# BoardTop.net
KiCad netlist of a schematic drawn in Altium Designer
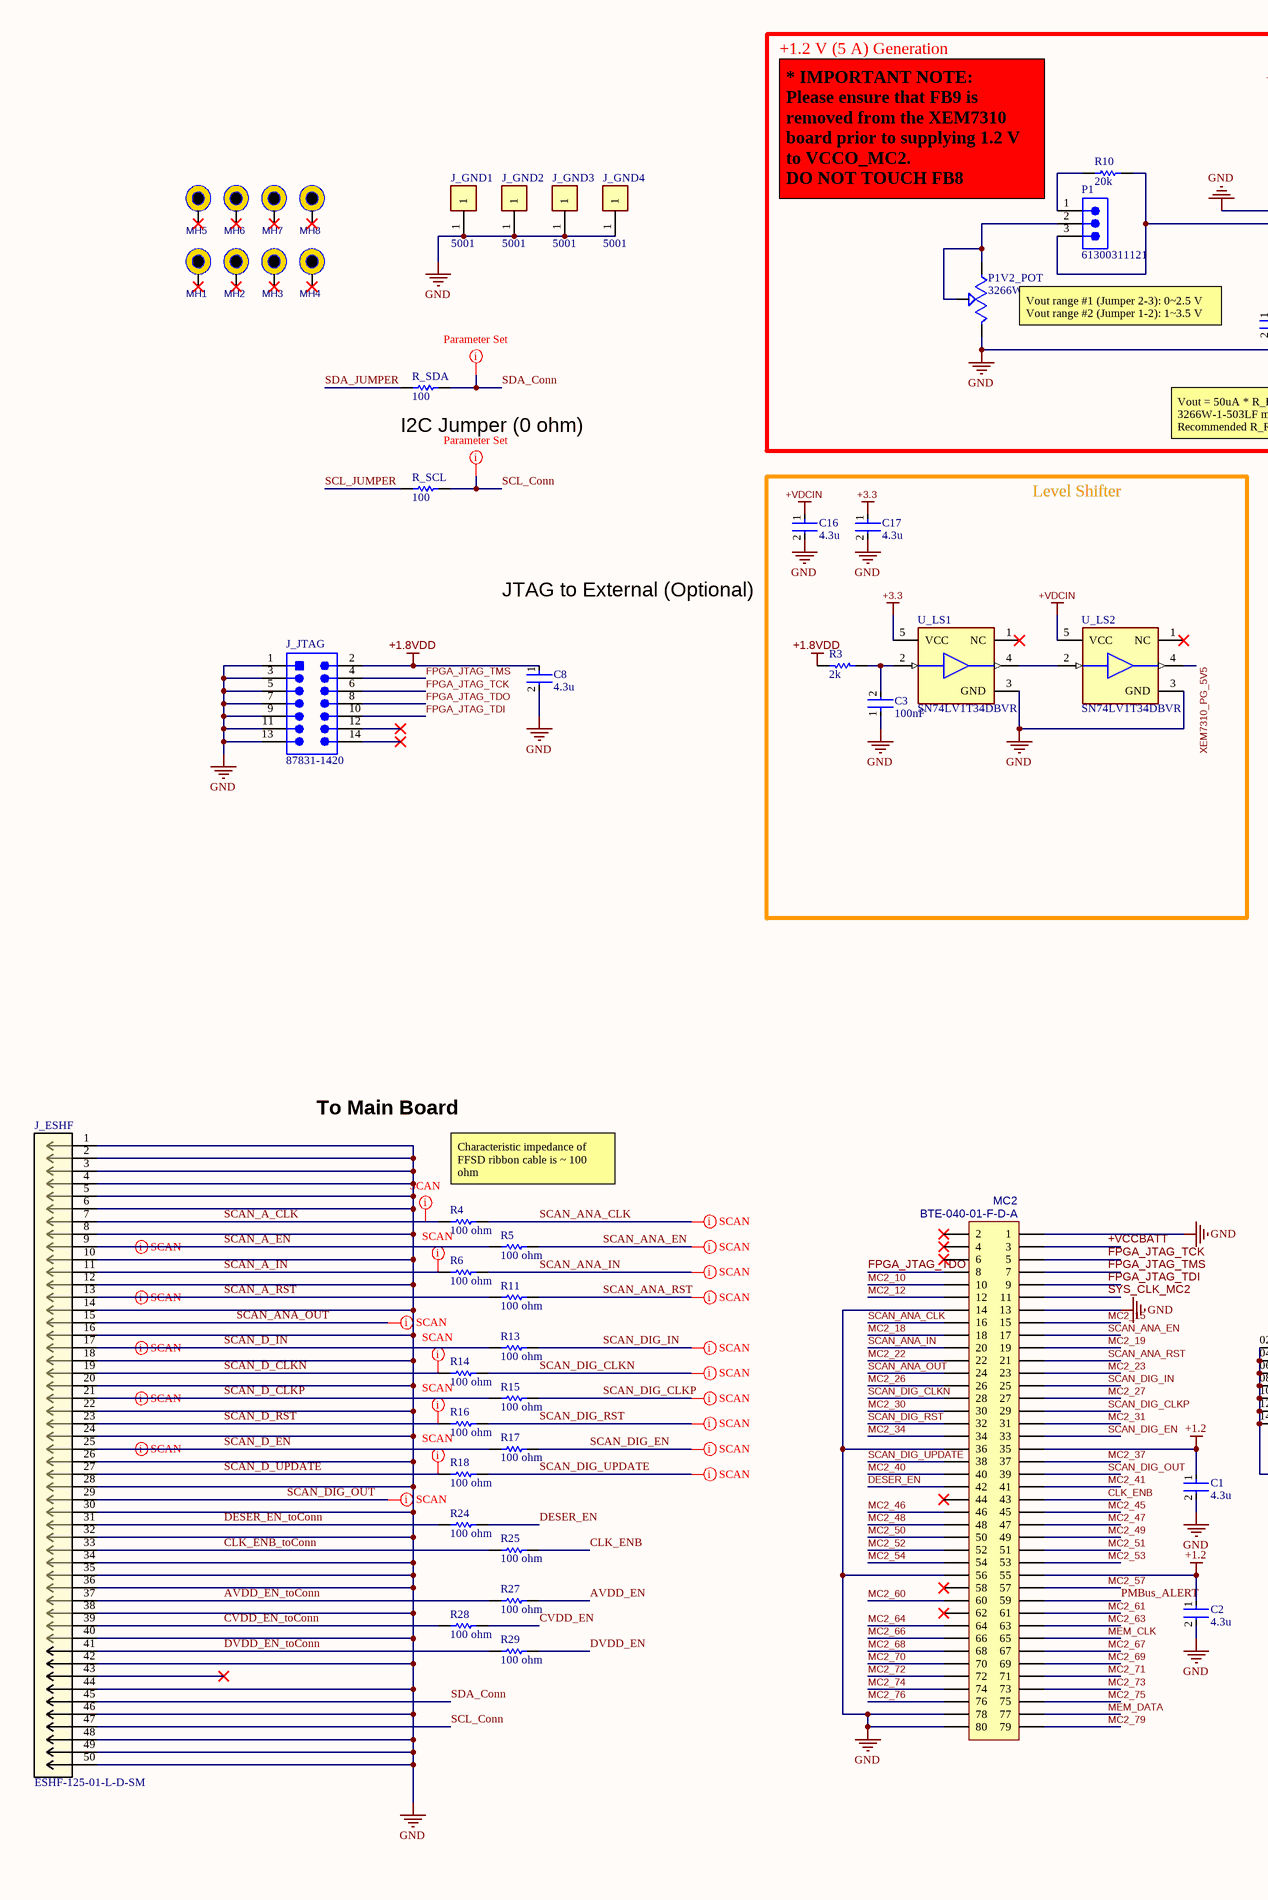
[diagram p0: BoardTop.SchDoc, left]
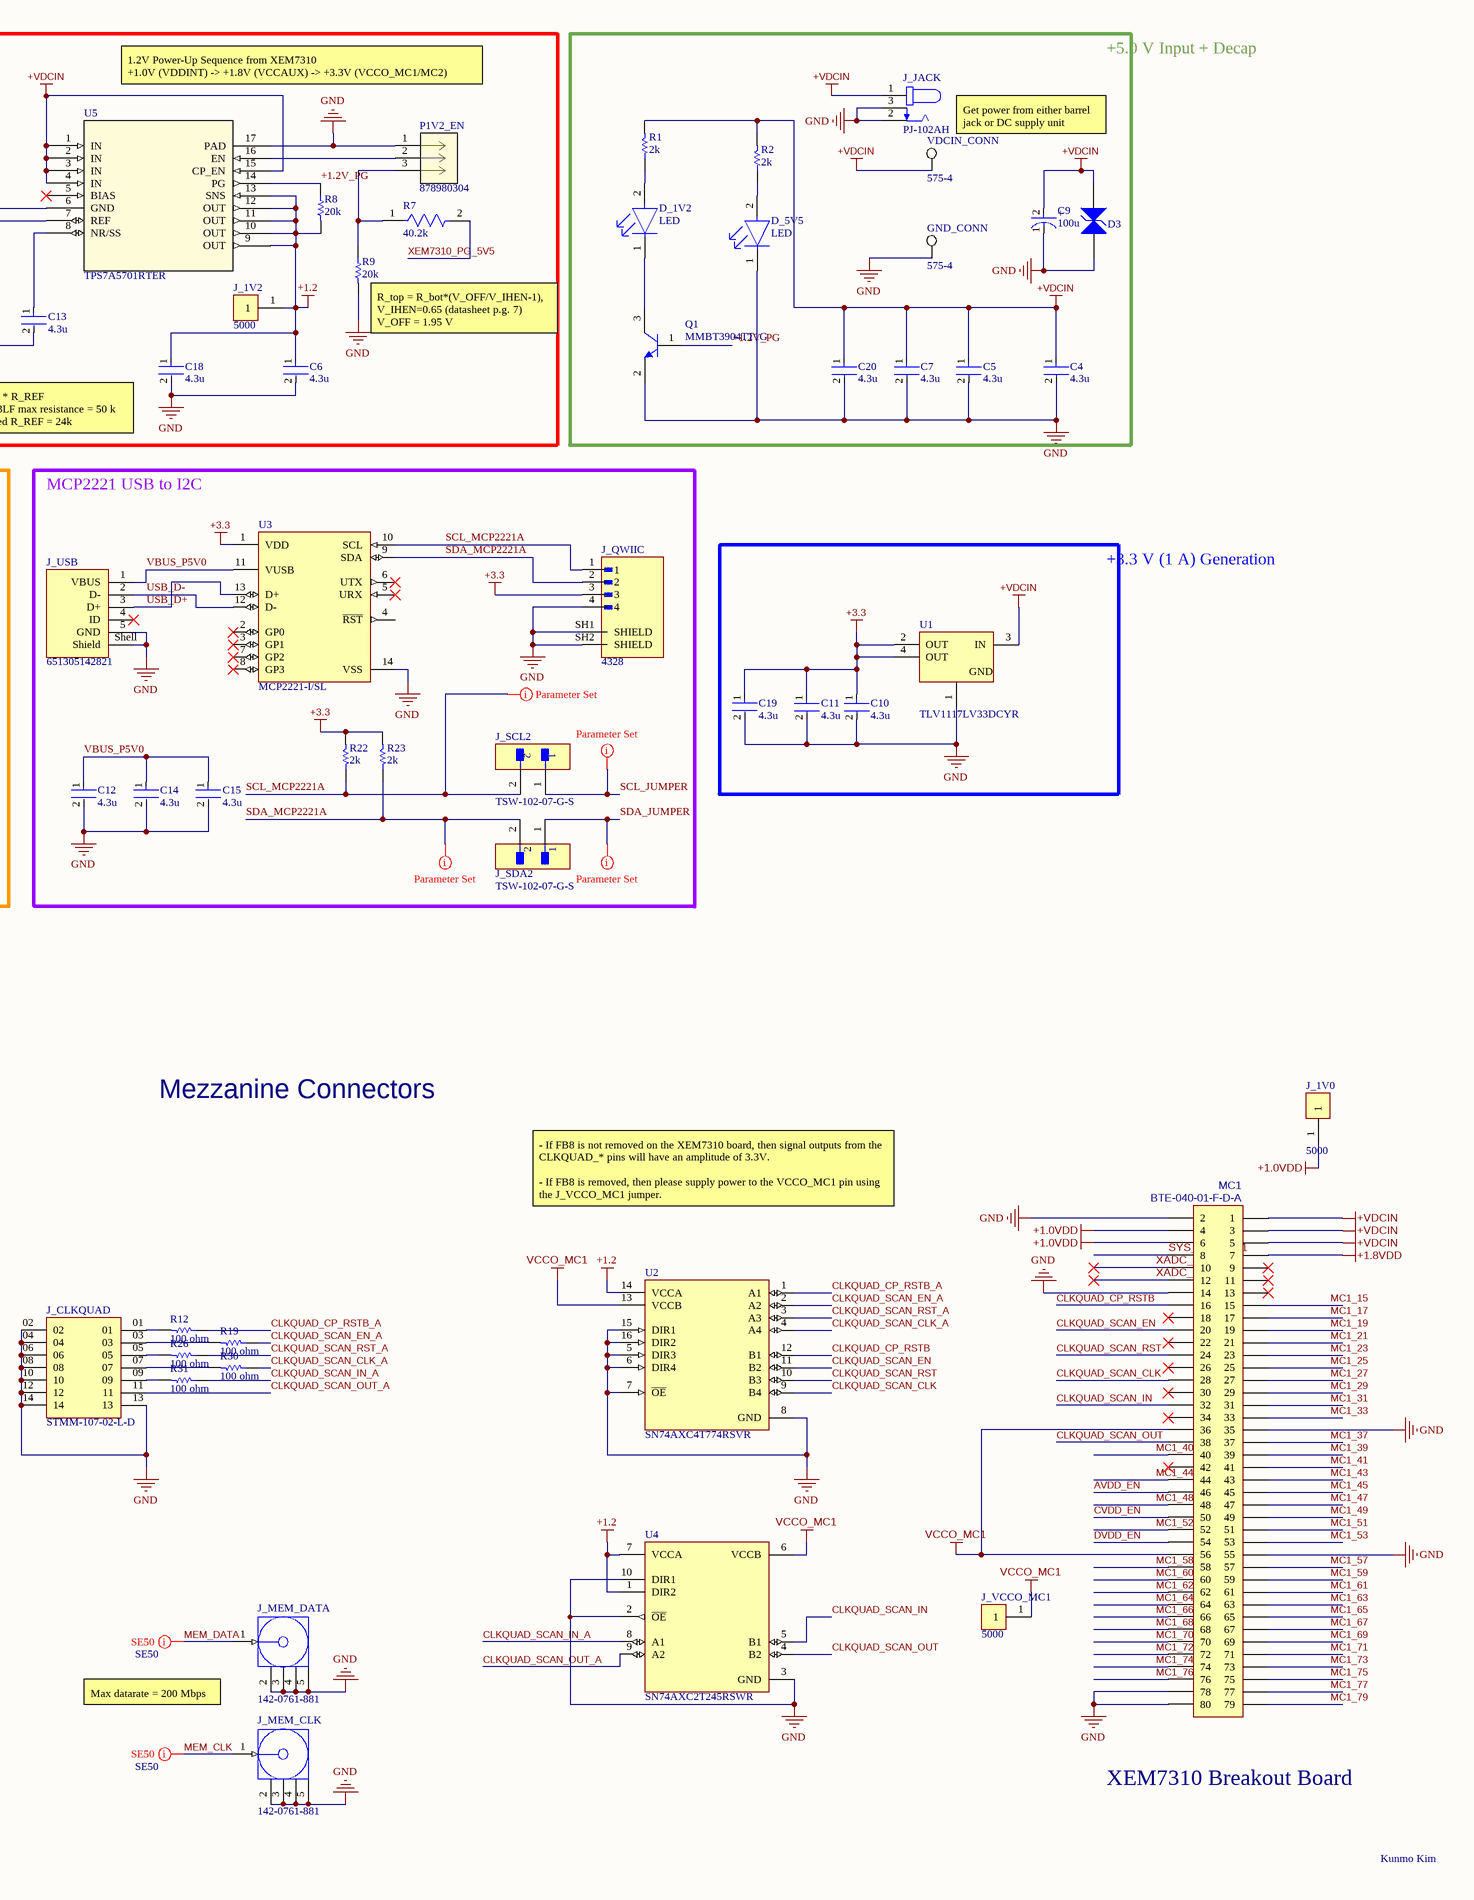
[diagram p1: BoardTop.SchDoc, right]

(export (version "E")
  (design (tool "Eeschema 10.0.6"))
  (components
    (comp (ref "C1")
      (value "4.3u")
      (footprint "FP-LLL1U4-0_05-IPC_C")
      (description "Cap Ceramic Monolithic 4.3uF 20% 4V X5R 15% 02404 (0610M)")
      (fields (field (name "TOLERANCE") "20%"))
      (libsource (lib "Altium Content Vault") (part "b4654b650e69147ec39a6b967a45e02"))
    )
    (comp (ref "C2")
      (value "4.3u")
      (footprint "FP-LLL1U4-0_05-IPC_C")
      (description "Cap Ceramic Monolithic 4.3uF 20% 4V X5R 15% 02404 (0610M)")
      (fields (field (name "TOLERANCE") "20%"))
      (libsource (lib "Altium Content Vault") (part "b4654b650e69147ec39a6b967a45e02"))
    )
    (comp (ref "C3")
      (value "100nF")
      (footprint "FP-0603-L_1_6_0_15-W_0_81-MFG")
      (description "General Purpose Ceramic Capacitor, 0603, 100nF, 10%, X7R, 15%, 50V")
      (fields (field (name "TOLERANCE") "10%") (field (name "VOLTAGE") "50V"))
      (libsource (lib "Altium Content Vault") (part "02cd4be3c70576c341d710602a673aa"))
    )
    (comp (ref "C4")
      (value "4.3u")
      (footprint "FP-LLL1U4-0_05-IPC_C")
      (description "Cap Ceramic Monolithic 4.3uF 20% 4V X5R 15% 02404 (0610M)")
      (fields (field (name "TOLERANCE") "20%"))
      (libsource (lib "Altium Content Vault") (part "b4654b650e69147ec39a6b967a45e02"))
    )
    (comp (ref "C5")
      (value "4.3u")
      (footprint "FP-LLL1U4-0_05-IPC_C")
      (description "Cap Ceramic Monolithic 4.3uF 20% 4V X5R 15% 02404 (0610M)")
      (fields (field (name "TOLERANCE") "20%"))
      (libsource (lib "Altium Content Vault") (part "b4654b650e69147ec39a6b967a45e02"))
    )
    (comp (ref "C6")
      (value "4.3u")
      (footprint "FP-LLL1U4-0_05-IPC_C")
      (description "Cap Ceramic Monolithic 4.3uF 20% 4V X5R 15% 02404 (0610M)")
      (fields (field (name "TOLERANCE") "20%"))
      (libsource (lib "Altium Content Vault") (part "b4654b650e69147ec39a6b967a45e02"))
    )
    (comp (ref "C7")
      (value "4.3u")
      (footprint "FP-LLL1U4-0_05-IPC_C")
      (description "Cap Ceramic Monolithic 4.3uF 20% 4V X5R 15% 02404 (0610M)")
      (fields (field (name "TOLERANCE") "20%"))
      (libsource (lib "Altium Content Vault") (part "b4654b650e69147ec39a6b967a45e02"))
    )
    (comp (ref "C8")
      (value "4.3u")
      (footprint "FP-LLL1U4-0_05-IPC_C")
      (description "Cap Ceramic Monolithic 4.3uF 20% 4V X5R 15% 02404 (0610M)")
      (fields (field (name "TOLERANCE") "20%"))
      (libsource (lib "Altium Content Vault") (part "b4654b650e69147ec39a6b967a45e02"))
    )
    (comp (ref "C9")
      (value "100u")
      (footprint "FP-CX-MFG")
      (description "CAP ALUM POLY 100UF 20% 6.3V SMD")
      (fields (field (name "VOLTAGE") "6.3V") (field (name "TOLERANCE") "20%"))
      (libsource (lib "cap_SP_100uF") (part "CMP-05427-000056-1"))
    )
    (comp (ref "C10")
      (value "4.3u")
      (footprint "FP-LLL1U4-0_05-IPC_C")
      (description "Cap Ceramic Monolithic 4.3uF 20% 4V X5R 15% 02404 (0610M)")
      (fields (field (name "TOLERANCE") "20%"))
      (libsource (lib "Altium Content Vault") (part "b4654b650e69147ec39a6b967a45e02"))
    )
    (comp (ref "C11")
      (value "4.3u")
      (footprint "FP-LLL1U4-0_05-IPC_C")
      (description "Cap Ceramic Monolithic 4.3uF 20% 4V X5R 15% 02404 (0610M)")
      (fields (field (name "TOLERANCE") "20%"))
      (libsource (lib "Altium Content Vault") (part "b4654b650e69147ec39a6b967a45e02"))
    )
    (comp (ref "C12")
      (value "4.3u")
      (footprint "FP-LLL1U4-0_05-IPC_C")
      (description "Cap Ceramic Monolithic 4.3uF 20% 4V X5R 15% 02404 (0610M)")
      (fields (field (name "TOLERANCE") "20%"))
      (libsource (lib "Altium Content Vault") (part "b4654b650e69147ec39a6b967a45e02"))
    )
    (comp (ref "C13")
      (value "4.3u")
      (footprint "FP-LLL1U4-0_05-IPC_C")
      (description "Cap Ceramic Monolithic 4.3uF 20% 4V X5R 15% 02404 (0610M)")
      (fields (field (name "TOLERANCE") "20%"))
      (libsource (lib "Altium Content Vault") (part "b4654b650e69147ec39a6b967a45e02"))
    )
    (comp (ref "C14")
      (value "4.3u")
      (footprint "FP-LLL1U4-0_05-IPC_C")
      (description "Cap Ceramic Monolithic 4.3uF 20% 4V X5R 15% 02404 (0610M)")
      (fields (field (name "TOLERANCE") "20%"))
      (libsource (lib "Altium Content Vault") (part "b4654b650e69147ec39a6b967a45e02"))
    )
    (comp (ref "C15")
      (value "4.3u")
      (footprint "FP-LLL1U4-0_05-IPC_C")
      (description "Cap Ceramic Monolithic 4.3uF 20% 4V X5R 15% 02404 (0610M)")
      (fields (field (name "TOLERANCE") "20%"))
      (libsource (lib "Altium Content Vault") (part "b4654b650e69147ec39a6b967a45e02"))
    )
    (comp (ref "C16")
      (value "4.3u")
      (footprint "FP-LLL1U4-0_05-IPC_C")
      (description "Cap Ceramic Monolithic 4.3uF 20% 4V X5R 15% 02404 (0610M)")
      (fields (field (name "TOLERANCE") "20%"))
      (libsource (lib "Altium Content Vault") (part "b4654b650e69147ec39a6b967a45e02"))
    )
    (comp (ref "C17")
      (value "4.3u")
      (footprint "FP-LLL1U4-0_05-IPC_C")
      (description "Cap Ceramic Monolithic 4.3uF 20% 4V X5R 15% 02404 (0610M)")
      (fields (field (name "TOLERANCE") "20%"))
      (libsource (lib "Altium Content Vault") (part "b4654b650e69147ec39a6b967a45e02"))
    )
    (comp (ref "C18")
      (value "4.3u")
      (footprint "FP-LLL1U4-0_05-IPC_C")
      (description "Cap Ceramic Monolithic 4.3uF 20% 4V X5R 15% 02404 (0610M)")
      (fields (field (name "TOLERANCE") "20%"))
      (libsource (lib "Altium Content Vault") (part "b4654b650e69147ec39a6b967a45e02"))
    )
    (comp (ref "C19")
      (value "4.3u")
      (footprint "FP-LLL1U4-0_05-IPC_C")
      (description "Cap Ceramic Monolithic 4.3uF 20% 4V X5R 15% 02404 (0610M)")
      (fields (field (name "TOLERANCE") "20%"))
      (libsource (lib "Altium Content Vault") (part "b4654b650e69147ec39a6b967a45e02"))
    )
    (comp (ref "C20")
      (value "4.3u")
      (footprint "FP-LLL1U4-0_05-IPC_C")
      (description "Cap Ceramic Monolithic 4.3uF 20% 4V X5R 15% 02404 (0610M)")
      (fields (field (name "TOLERANCE") "20%"))
      (libsource (lib "Altium Content Vault") (part "b4654b650e69147ec39a6b967a45e02"))
    )
    (comp (ref "D3")
      (value "SMAJ6.0CAHE3/5A")
      (footprint "VISH-DO-214AC-2_L")
      (fields (field (name "MANUFACTURER") "Vishay Semiconductor"))
      (libsource (lib "SMAJ6p0CAHE3") (part "CMP-0548-00108-2"))
    )
    (comp (ref "D_1V2")
      (value "LED")
      (footprint "FP-LTST-C190KGKT-MFG")
      (description "LED GREEN CLEAR CHIP SMD")
      (libsource (lib "LTST-C190KGKT") (part "CMP-2000-05197-2"))
    )
    (comp (ref "D_5V5")
      (value "LED")
      (footprint "FP-LTST-C190KGKT-MFG")
      (description "LED GREEN CLEAR CHIP SMD")
      (libsource (lib "LTST-C190KGKT") (part "CMP-2000-05197-2"))
    )
    (comp (ref "GND_CONN")
      (value "575-4")
      (footprint "KSTN-575-4")
      (description "Banana Jack, Non-Insulated, 1-Pin THD, RoHS, Bulk")
      (fields (field (name "MANUFACTURER") "Keystone-Electronics"))
      (libsource (lib "Altium Content Vault") (part "TESTPOINT_WHITE"))
    )
    (comp (ref "J_1V0")
      (value "5000")
      (footprint "FP-5000-MFG")
      (description "PC TEST POINT MINIATURE RED")
      (libsource (lib "") (part "CMP-19636-000027-1_1"))
    )
    (comp (ref "J_1V2")
      (value "5000")
      (footprint "FP-5000-MFG")
      (description "PC TEST POINT MINIATURE RED")
      (libsource (lib "TP_5000") (part "CMP-19636-000027-1"))
    )
    (comp (ref "J_CLKQUAD")
      (value "STMM-107-02-L-D")
      (footprint "SAMTEC_STMM-107-02-L-D")
      (description "Connector Header Surface Mount 14 position 0.079 (2.00mm)")
      (fields (field (name "MF") "Samtec") (field (name "DIGI-KEY_PART_NUMBER") "STMM-107-02-L-D-SM-TR-ND"))
      (libsource (lib "STMM-107-02-L-D") (part "STMM-107-02-L-D"))
    )
    (comp (ref "J_ESHF")
      (value "ESHF-125-01-L-D-SM")
      (footprint "CONN_ESHF-125-01-x-D-SM_SAI")
      (description "No Description Available")
      (libsource (lib "FPGA_breakout_board") (part "ESHF-125-01-L-D-SM"))
    )
    (comp (ref "J_GND1")
      (value "5001")
      (footprint "FP-5001-MFG")
      (description "PC TEST POINT MINIATURE BLACK")
      (libsource (lib "TP_5001") (part "CMP-2000-05181-2"))
    )
    (comp (ref "J_GND2")
      (value "5001")
      (footprint "FP-5001-MFG")
      (description "PC TEST POINT MINIATURE BLACK")
      (libsource (lib "TP_5001") (part "CMP-2000-05181-2"))
    )
    (comp (ref "J_GND3")
      (value "5001")
      (footprint "FP-5001-MFG")
      (description "PC TEST POINT MINIATURE BLACK")
      (libsource (lib "TP_5001") (part "CMP-2000-05181-2"))
    )
    (comp (ref "J_GND4")
      (value "5001")
      (footprint "FP-5001-MFG")
      (description "PC TEST POINT MINIATURE BLACK")
      (libsource (lib "TP_5001") (part "CMP-2000-05181-2"))
    )
    (comp (ref "J_JACK")
      (value "PJ-102AH")
      (footprint "CUI_PJ-102AH")
      (description "2.0 x 6.5 mm, 5.0 A, Horizontal, Through Hole, Tapered Pins, Dc Power Jack Connector")
      (fields (field (name "MF") "Same Sky"))
      (libsource (lib "PJ-102AH") (part "PJ-102AH"))
    )
    (comp (ref "J_JTAG")
      (value "87831-1420")
      (footprint "MOLEX-87831-1420_V")
      (description "Header, Pitch 2 mm, 2 x 7 Position, Height 6.4 mm, Tail Length 2.5 mm, -55 to 105 degC, RoHS, Tube")
      (fields (field (name "MANUFACTURER") "Molex"))
      (libsource (lib "JTAG_connector") (part "CMP-2000-05240-1"))
    )
    (comp (ref "J_MEM_CLK")
      (value "142-0761-881")
      (footprint "EMSN-142-0761-881-5_V")
      (fields (field (name "MANUFACTURER") "Emerson Network Power"))
      (libsource (lib "SMA_connector_A") (part "CMP-0839-00001-1"))
    )
    (comp (ref "J_MEM_DATA")
      (value "142-0761-881")
      (footprint "EMSN-142-0761-881-5_V")
      (fields (field (name "MANUFACTURER") "Emerson Network Power"))
      (libsource (lib "SMA_connector_A") (part "CMP-0839-00001-1"))
    )
    (comp (ref "J_QWIIC")
      (value "4328")
      (footprint "ADAFRUIT_4328")
      (description "Adafruit Accessories JST SH 4-pin Vertical Connector (10-pack) - Qwiic Compatible")
      (fields (field (name "MF") "Adafruit"))
      (libsource (lib "4328") (part "4328"))
    )
    (comp (ref "J_SCL2")
      (value "TSW-102-07-G-S")
      (footprint "FP-TSW-102-07-G-S-MFG")
      (description "CONN HEADER VERT 2POS 2.54MM")
      (fields
        (field (name "MANUFACTURER") "Samtec")
        (field (name "OCTOPART") "https://octopart.com/tsw-102-07-g-s-samtec-272197")
      )
      (libsource (lib "") (part "3bc925449376181038e59eaffc5286c_1"))
    )
    (comp (ref "J_SDA2")
      (value "TSW-102-07-G-S")
      (footprint "FP-TSW-102-07-G-S-MFG")
      (description "CONN HEADER VERT 2POS 2.54MM")
      (fields
        (field (name "MANUFACTURER") "Samtec")
        (field (name "OCTOPART") "https://octopart.com/tsw-102-07-g-s-samtec-272197")
      )
      (libsource (lib "Altium Content Vault") (part "3bc925449376181038e59eaffc5286c"))
    )
    (comp (ref "J_USB")
      (value "651305142821")
      (footprint "651305142821")
      (libsource (lib "Altium Content Vault") (part "Mini USB 2.0_Type AB_Receptacle_1 Port"))
    )
    (comp (ref "J_VCCO_MC1")
      (value "5000")
      (footprint "FP-5000-MFG")
      (description "PC TEST POINT MINIATURE RED")
      (libsource (lib "TP_5000") (part "CMP-19636-000027-1"))
    )
    (comp (ref "MC1")
      (value "BTE-040-01-F-D-A")
      (footprint "BTE-040")
      (description "0.8mm high-density header")
      (fields (field (name "MANUFACTURER") "Samtec") (field (name "PARTNUMBER") "000059"))
      (libsource (lib "BRK7010") (part "BTE040"))
    )
    (comp (ref "MC2")
      (value "BTE-040-01-F-D-A")
      (footprint "BTE-040")
      (description "0.8mm high-density header")
      (fields (field (name "MANUFACTURER") "Samtec") (field (name "PARTNUMBER") "000059"))
      (libsource (lib "BRK7010") (part "BTE040"))
    )
    (comp (ref "MH1")
      (value "MTG")
      (footprint "MTG-3.2/6.5-PTH")
      (description "Mounting hole")
      (libsource (lib "BRK8305") (part "MTG"))
    )
    (comp (ref "MH2")
      (value "MTG")
      (footprint "MTG-3.2/6.5-PTH")
      (description "Mounting hole")
      (libsource (lib "BRK8305") (part "MTG"))
    )
    (comp (ref "MH3")
      (value "MTG")
      (footprint "MTG-3.2/6.5-PTH")
      (description "Mounting hole")
      (libsource (lib "BRK8305") (part "MTG"))
    )
    (comp (ref "MH4")
      (value "MTG")
      (footprint "MTG-3.2/6.5-PTH")
      (description "Mounting hole")
      (libsource (lib "BRK8305") (part "MTG"))
    )
    (comp (ref "MH5")
      (value "MTG")
      (footprint "MTG-3.2/6.5-PTH")
      (description "Mounting hole")
      (libsource (lib "BRK8305") (part "MTG"))
    )
    (comp (ref "MH6")
      (value "MTG")
      (footprint "MTG-3.2/6.5-PTH")
      (description "Mounting hole")
      (libsource (lib "BRK8305") (part "MTG"))
    )
    (comp (ref "MH7")
      (value "MTG")
      (footprint "MTG-3.2/6.5-PTH")
      (description "Mounting hole")
      (libsource (lib "BRK8305") (part "MTG"))
    )
    (comp (ref "MH8")
      (value "MTG")
      (footprint "MTG-3.2/6.5-PTH")
      (description "Mounting hole")
      (libsource (lib "BRK8305") (part "MTG"))
    )
    (comp (ref "P1")
      (value "61300311121")
      (footprint "61300311121")
      (libsource (lib "Altium Content Vault") (part "Header_Male_1R_03P"))
    )
    (comp (ref "P1V2_EN")
      (value "878980304")
      (footprint "CONN03_87898_M-5p84_MOL")
      (description "No Description Available")
      (libsource (lib "878980304") (part "878980304"))
    )
    (comp (ref "P1V2_POT")
      (value "3266W-1-503LF")
      (footprint "TRIM_3266W-1-503LF")
      (description "50 kOhms 0.25W, 1/4W PC Pins Through Hole Trimmer Potentiometer Cermet 12 Turn Top Adjustment")
      (fields (field (name "MF") "Bourns"))
      (libsource (lib "3266W-1-503LF") (part "3266W-1-503LF"))
    )
    (comp (ref "Q1")
      (value "MMBT3904TT1G")
      (footprint "ONSC-SC-75-3-463-01_V")
      (description "General Purpose Transistor, NPN Silicon, 3-Pin SC-75, Pb-Free, Tape and Reel")
      (fields (field (name "MANUFACTURER") "On Semiconductor"))
      (libsource (lib "Altium Content Vault") (part "ONSC-NPN-B1E2C3-3"))
    )
    (comp (ref "R1")
      (value "2k")
      (footprint "RESC3216X70X50NL05T20")
      (fields (field (name "PART NUMBER") "ERJ-8ENF2001V") (field (name "MANUFACTURER") "Panasonic"))
      (libsource (lib "Altium Content Vault") (part "RES"))
    )
    (comp (ref "R2")
      (value "2k")
      (footprint "RESC3216X70X50NL05T20")
      (fields (field (name "PART NUMBER") "ERJ-8ENF2001V") (field (name "MANUFACTURER") "Panasonic"))
      (libsource (lib "Altium Content Vault") (part "RES"))
    )
    (comp (ref "R3")
      (value "2k")
      (footprint "RESC3216X70X50NL05T20")
      (fields (field (name "PART NUMBER") "ERJ-8ENF2001V") (field (name "MANUFACTURER") "Panasonic"))
      (libsource (lib "Altium Content Vault") (part "RES"))
    )
    (comp (ref "R4")
      (value "100 ohm")
      (footprint "RESC1005X40X25ML05T05")
      (description "Chip Resistor, 100 Ohm, +/- 1%, 100 mW, -55 to 155 degC, 0402 (1005 Metric), RoHS, Tape and Reel")
      (fields (field (name "MANUFACTURER") "Basic Passives") (field (name "TOLERANCE") "1%"))
      (libsource (lib "Altium Content Vault") (part "RES-2"))
    )
    (comp (ref "R5")
      (value "100 ohm")
      (footprint "RESC1005X40X25ML05T05")
      (description "Chip Resistor, 100 Ohm, +/- 1%, 100 mW, -55 to 155 degC, 0402 (1005 Metric), RoHS, Tape and Reel")
      (fields (field (name "MANUFACTURER") "Basic Passives") (field (name "TOLERANCE") "1%"))
      (libsource (lib "Altium Content Vault") (part "RES-2"))
    )
    (comp (ref "R6")
      (value "100 ohm")
      (footprint "RESC1005X40X25ML05T05")
      (description "Chip Resistor, 100 Ohm, +/- 1%, 100 mW, -55 to 155 degC, 0402 (1005 Metric), RoHS, Tape and Reel")
      (fields (field (name "MANUFACTURER") "Basic Passives") (field (name "TOLERANCE") "1%"))
      (libsource (lib "Altium Content Vault") (part "RES-2"))
    )
    (comp (ref "R7")
      (value "40.2k")
      (footprint "FP-ERJ3EK-IPC_C")
      (description "RES SMD 40.2K OHM 1% 1/10W 0603")
      (fields (field (name "TOLERANCE") "1%"))
      (libsource (lib "Altium Content Vault") (part "1029c3af85768c4190bb7ad29bc67b5"))
    )
    (comp (ref "R8")
      (value "20k")
      (footprint "RESC1608X55X30ML15T15")
      (fields (field (name "PART NUMBER") "ERJ-3EKF2002V") (field (name "MANUFACTURER") "Panasonic"))
      (libsource (lib "Altium Content Vault") (part "RES"))
    )
    (comp (ref "R9")
      (value "20k")
      (footprint "RESC1608X55X30ML15T15")
      (fields (field (name "PART NUMBER") "ERJ-3EKF2002V") (field (name "MANUFACTURER") "Panasonic"))
      (libsource (lib "Altium Content Vault") (part "RES"))
    )
    (comp (ref "R10")
      (value "20k")
      (footprint "RESC1608X55X30ML15T15")
      (fields (field (name "PART NUMBER") "ERJ-3EKF2002V") (field (name "MANUFACTURER") "Panasonic"))
      (libsource (lib "Altium Content Vault") (part "RES"))
    )
    (comp (ref "R11")
      (value "100 ohm")
      (footprint "RESC1005X40X25ML05T05")
      (description "Chip Resistor, 100 Ohm, +/- 1%, 100 mW, -55 to 155 degC, 0402 (1005 Metric), RoHS, Tape and Reel")
      (fields (field (name "MANUFACTURER") "Basic Passives") (field (name "TOLERANCE") "1%"))
      (libsource (lib "Altium Content Vault") (part "RES-2"))
    )
    (comp (ref "R12")
      (value "100 ohm")
      (footprint "RESC1005X40X25ML05T05")
      (description "Chip Resistor, 100 Ohm, +/- 1%, 100 mW, -55 to 155 degC, 0402 (1005 Metric), RoHS, Tape and Reel")
      (fields (field (name "MANUFACTURER") "Basic Passives") (field (name "TOLERANCE") "1%"))
      (libsource (lib "Altium Content Vault") (part "RES-2"))
    )
    (comp (ref "R13")
      (value "100 ohm")
      (footprint "RESC1005X40X25ML05T05")
      (description "Chip Resistor, 100 Ohm, +/- 1%, 100 mW, -55 to 155 degC, 0402 (1005 Metric), RoHS, Tape and Reel")
      (fields (field (name "MANUFACTURER") "Basic Passives") (field (name "TOLERANCE") "1%"))
      (libsource (lib "Altium Content Vault") (part "RES-2"))
    )
    (comp (ref "R14")
      (value "100 ohm")
      (footprint "RESC1005X40X25ML05T05")
      (description "Chip Resistor, 100 Ohm, +/- 1%, 100 mW, -55 to 155 degC, 0402 (1005 Metric), RoHS, Tape and Reel")
      (fields (field (name "MANUFACTURER") "Basic Passives") (field (name "TOLERANCE") "1%"))
      (libsource (lib "Altium Content Vault") (part "RES-2"))
    )
    (comp (ref "R15")
      (value "100 ohm")
      (footprint "RESC1005X40X25ML05T05")
      (description "Chip Resistor, 100 Ohm, +/- 1%, 100 mW, -55 to 155 degC, 0402 (1005 Metric), RoHS, Tape and Reel")
      (fields (field (name "MANUFACTURER") "Basic Passives") (field (name "TOLERANCE") "1%"))
      (libsource (lib "Altium Content Vault") (part "RES-2"))
    )
    (comp (ref "R16")
      (value "100 ohm")
      (footprint "RESC1005X40X25ML05T05")
      (description "Chip Resistor, 100 Ohm, +/- 1%, 100 mW, -55 to 155 degC, 0402 (1005 Metric), RoHS, Tape and Reel")
      (fields (field (name "MANUFACTURER") "Basic Passives") (field (name "TOLERANCE") "1%"))
      (libsource (lib "Altium Content Vault") (part "RES-2"))
    )
    (comp (ref "R17")
      (value "100 ohm")
      (footprint "RESC1005X40X25ML05T05")
      (description "Chip Resistor, 100 Ohm, +/- 1%, 100 mW, -55 to 155 degC, 0402 (1005 Metric), RoHS, Tape and Reel")
      (fields (field (name "MANUFACTURER") "Basic Passives") (field (name "TOLERANCE") "1%"))
      (libsource (lib "Altium Content Vault") (part "RES-2"))
    )
    (comp (ref "R18")
      (value "100 ohm")
      (footprint "RESC1005X40X25ML05T05")
      (description "Chip Resistor, 100 Ohm, +/- 1%, 100 mW, -55 to 155 degC, 0402 (1005 Metric), RoHS, Tape and Reel")
      (fields (field (name "MANUFACTURER") "Basic Passives") (field (name "TOLERANCE") "1%"))
      (libsource (lib "Altium Content Vault") (part "RES-2"))
    )
    (comp (ref "R19")
      (value "100 ohm")
      (footprint "RESC1005X40X25ML05T05")
      (description "Chip Resistor, 100 Ohm, +/- 1%, 100 mW, -55 to 155 degC, 0402 (1005 Metric), RoHS, Tape and Reel")
      (fields (field (name "MANUFACTURER") "Basic Passives") (field (name "TOLERANCE") "1%"))
      (libsource (lib "Altium Content Vault") (part "RES-2"))
    )
    (comp (ref "R22")
      (value "2k")
      (footprint "RESC3216X70X50NL05T20")
      (fields (field (name "PART NUMBER") "ERJ-8ENF2001V") (field (name "MANUFACTURER") "Panasonic"))
      (libsource (lib "Altium Content Vault") (part "RES"))
    )
    (comp (ref "R23")
      (value "2k")
      (footprint "RESC3216X70X50NL05T20")
      (fields (field (name "PART NUMBER") "ERJ-8ENF2001V") (field (name "MANUFACTURER") "Panasonic"))
      (libsource (lib "Altium Content Vault") (part "RES"))
    )
    (comp (ref "R24")
      (value "100 ohm")
      (footprint "RESC1005X40X25ML05T05")
      (description "Chip Resistor, 100 Ohm, +/- 1%, 100 mW, -55 to 155 degC, 0402 (1005 Metric), RoHS, Tape and Reel")
      (fields (field (name "MANUFACTURER") "Basic Passives") (field (name "TOLERANCE") "1%"))
      (libsource (lib "Altium Content Vault") (part "RES-2"))
    )
    (comp (ref "R25")
      (value "100 ohm")
      (footprint "RESC1005X40X25ML05T05")
      (description "Chip Resistor, 100 Ohm, +/- 1%, 100 mW, -55 to 155 degC, 0402 (1005 Metric), RoHS, Tape and Reel")
      (fields (field (name "MANUFACTURER") "Basic Passives") (field (name "TOLERANCE") "1%"))
      (libsource (lib "Altium Content Vault") (part "RES-2"))
    )
    (comp (ref "R26")
      (value "100 ohm")
      (footprint "RESC1005X40X25ML05T05")
      (description "Chip Resistor, 100 Ohm, +/- 1%, 100 mW, -55 to 155 degC, 0402 (1005 Metric), RoHS, Tape and Reel")
      (fields (field (name "MANUFACTURER") "Basic Passives") (field (name "TOLERANCE") "1%"))
      (libsource (lib "Altium Content Vault") (part "RES-2"))
    )
    (comp (ref "R27")
      (value "100 ohm")
      (footprint "RESC1005X40X25ML05T05")
      (description "Chip Resistor, 100 Ohm, +/- 1%, 100 mW, -55 to 155 degC, 0402 (1005 Metric), RoHS, Tape and Reel")
      (fields (field (name "MANUFACTURER") "Basic Passives") (field (name "TOLERANCE") "1%"))
      (libsource (lib "Altium Content Vault") (part "RES-2"))
    )
    (comp (ref "R28")
      (value "100 ohm")
      (footprint "RESC1005X40X25ML05T05")
      (description "Chip Resistor, 100 Ohm, +/- 1%, 100 mW, -55 to 155 degC, 0402 (1005 Metric), RoHS, Tape and Reel")
      (fields (field (name "MANUFACTURER") "Basic Passives") (field (name "TOLERANCE") "1%"))
      (libsource (lib "Altium Content Vault") (part "RES-2"))
    )
    (comp (ref "R29")
      (value "100 ohm")
      (footprint "RESC1005X40X25ML05T05")
      (description "Chip Resistor, 100 Ohm, +/- 1%, 100 mW, -55 to 155 degC, 0402 (1005 Metric), RoHS, Tape and Reel")
      (fields (field (name "MANUFACTURER") "Basic Passives") (field (name "TOLERANCE") "1%"))
      (libsource (lib "Altium Content Vault") (part "RES-2"))
    )
    (comp (ref "R30")
      (value "100 ohm")
      (footprint "RESC1005X40X25ML05T05")
      (description "Chip Resistor, 100 Ohm, +/- 1%, 100 mW, -55 to 155 degC, 0402 (1005 Metric), RoHS, Tape and Reel")
      (fields (field (name "MANUFACTURER") "Basic Passives") (field (name "TOLERANCE") "1%"))
      (libsource (lib "Altium Content Vault") (part "RES-2"))
    )
    (comp (ref "R31")
      (value "100 ohm")
      (footprint "RESC1005X40X25ML05T05")
      (description "Chip Resistor, 100 Ohm, +/- 1%, 100 mW, -55 to 155 degC, 0402 (1005 Metric), RoHS, Tape and Reel")
      (fields (field (name "MANUFACTURER") "Basic Passives") (field (name "TOLERANCE") "1%"))
      (libsource (lib "Altium Content Vault") (part "RES-2"))
    )
    (comp (ref "R_SCL")
      (value "100")
      (footprint "RESC1608X55X30LL15T15")
      (fields (field (name "MANUFACTURER") "Panasonic") (field (name "PART NUMBER") "ERJ-3EKF1000V"))
      (libsource (lib "Altium Content Vault") (part "RES"))
    )
    (comp (ref "R_SDA")
      (value "100")
      (footprint "RESC1608X55X30LL15T15")
      (fields (field (name "MANUFACTURER") "Panasonic") (field (name "PART NUMBER") "ERJ-3EKF1000V"))
      (libsource (lib "Altium Content Vault") (part "RES"))
    )
    (comp (ref "U1")
      (value "TLV1117LV33DCYR")
      (footprint "DCY0004A_N")
      (fields (field (name "MANUFACTURER") "Texas Instruments"))
      (libsource (lib "Altium Content Vault") (part "TI-TLV1117LV33DCY4"))
    )
    (comp (ref "U2")
      (value "SN74AXC4T774RSVR")
      (footprint "FP-RSV0016A-MFG")
      (description "IC LOGIC BUFFER/DRIVER")
      (libsource (lib "Altium Content Vault") (part "c5b569fa8cc74ee6501ffcc2755e21e"))
    )
    (comp (ref "U3")
      (value "MCP2221-I/SL")
      (footprint "FP-C04-065-SL-IPC_A")
      (description "IC USB TO I2C BRIDGE DEVICE 14SO")
      (libsource (lib "Altium Content Vault") (part "346ed09f11d0e27a5cfb8ccfcbed8cb"))
    )
    (comp (ref "U4")
      (value "SN74AXC2T245RSWR")
      (footprint "FP-RSW0010A-MFG")
      (description "DUAL-BIT, 2-DIR PIN DUAL-SUPPLY")
      (libsource (lib "Altium Content Vault") (part "83d821090a53739ef2c335e5778ad4a"))
    )
    (comp (ref "U5")
      (value "TPS7A5701RTER")
      (footprint "WQFN16_RTE_TEX")
      (description "No Description Available")
      (libsource (lib "TPS7A5701RTER") (part "TPS7A5701RTER"))
    )
    (comp (ref "U_LS1")
      (value "SN74LV1T34DBVR")
      (footprint "FP-DBV0005A-MFG")
      (description "IC BUF NON-INVERT 5.5V SOT23-5")
      (libsource (lib "SN74LV1T34") (part "CMP-0859-00123-4"))
    )
    (comp (ref "U_LS2")
      (value "SN74LV1T34DBVR")
      (footprint "FP-DBV0005A-MFG")
      (description "IC BUF NON-INVERT 5.5V SOT23-5")
      (libsource (lib "SN74LV1T34") (part "CMP-0859-00123-4"))
    )
    (comp (ref "VDCIN_CONN")
      (value "575-4")
      (footprint "KSTN-575-4")
      (description "Banana Jack, Non-Insulated, 1-Pin THD, RoHS, Bulk")
      (fields (field (name "MANUFACTURER") "Keystone-Electronics"))
      (libsource (lib "Altium Content Vault") (part "TESTPOINT_WHITE"))
    )
  )
  (nets
    (net (code "1") (name "+1.0VDD") (class "Default")
      (node (ref "J_1V0") (pin "1") (pinfunction "1_1") (pintype "passive"))
      (node (ref "MC1") (pin "4") (pinfunction "4_4") (pintype "passive"))
      (node (ref "MC1") (pin "6") (pinfunction "6_6") (pintype "passive"))
    )
    (net (code "2") (name "+1.2") (class "Default")
      (node (ref "C1") (pin "1") (pinfunction "1_1") (pintype "passive"))
      (node (ref "C18") (pin "1") (pinfunction "1_1") (pintype "passive"))
      (node (ref "C2") (pin "1") (pinfunction "1_1") (pintype "passive"))
      (node (ref "C6") (pin "1") (pinfunction "1_1") (pintype "passive"))
      (node (ref "J_1V2") (pin "1") (pinfunction "1_1") (pintype "passive"))
      (node (ref "MC2") (pin "35") (pinfunction "35_35") (pintype "passive"))
      (node (ref "MC2") (pin "55") (pinfunction "55_55") (pintype "passive"))
      (node (ref "R8") (pin "2") (pinfunction "2_2") (pintype "passive"))
      (node (ref "U2") (pin "14") (pinfunction "VCCA_14") (pintype "power_in"))
      (node (ref "U4") (pin "1") (pinfunction "DIR2_1") (pintype "passive"))
      (node (ref "U4") (pin "7") (pinfunction "VCCA_7") (pintype "power_in"))
      (node (ref "U5") (pin "10") (pinfunction "OUT_10") (pintype "output"))
      (node (ref "U5") (pin "11") (pinfunction "OUT_11") (pintype "output"))
      (node (ref "U5") (pin "12") (pinfunction "OUT_12") (pintype "output"))
      (node (ref "U5") (pin "13") (pinfunction "SNS_13") (pintype "input"))
      (node (ref "U5") (pin "9") (pinfunction "OUT_9") (pintype "output"))
    )
    (net (code "3") (name "+1.8VDD") (class "Default")
      (node (ref "C8") (pin "1") (pinfunction "1_1") (pintype "passive"))
      (node (ref "J_JTAG") (pin "2") (pinfunction "2_2") (pintype "passive"))
      (node (ref "MC1") (pin "7") (pinfunction "7_7") (pintype "passive"))
      (node (ref "R3") (pin "2") (pinfunction "2_2") (pintype "passive"))
    )
    (net (code "4") (name "+3.3") (class "Default")
      (node (ref "C10") (pin "1") (pinfunction "1_1") (pintype "passive"))
      (node (ref "C11") (pin "1") (pinfunction "1_1") (pintype "passive"))
      (node (ref "C17") (pin "1") (pinfunction "1_1") (pintype "passive"))
      (node (ref "C19") (pin "1") (pinfunction "1_1") (pintype "passive"))
      (node (ref "J_QWIIC") (pin "3") (pinfunction "3_3") (pintype "passive"))
      (node (ref "R22") (pin "2") (pinfunction "2_2") (pintype "passive"))
      (node (ref "R23") (pin "2") (pinfunction "2_2") (pintype "passive"))
      (node (ref "U1") (pin "2") (pinfunction "OUT_2") (pintype "power_in"))
      (node (ref "U1") (pin "4") (pinfunction "OUT_4") (pintype "power_in"))
      (node (ref "U3") (pin "1") (pinfunction "VDD_1") (pintype "power_in"))
      (node (ref "U_LS1") (pin "5") (pinfunction "VCC_5") (pintype "power_in"))
    )
    (net (code "5") (name "+VDCIN") (class "Default")
      (node (ref "C16") (pin "1") (pinfunction "1_1") (pintype "passive"))
      (node (ref "C20") (pin "1") (pinfunction "1_1") (pintype "passive"))
      (node (ref "C4") (pin "1") (pinfunction "1_1") (pintype "passive"))
      (node (ref "C5") (pin "1") (pinfunction "1_1") (pintype "passive"))
      (node (ref "C7") (pin "1") (pinfunction "1_1") (pintype "passive"))
      (node (ref "C9") (pin "2") (pinfunction "A_2") (pintype "passive"))
      (node (ref "D3") (pin "1") (pinfunction "A1_1") (pintype "passive"))
      (node (ref "J_JACK") (pin "1") (pinfunction "1_1") (pintype "passive"))
      (node (ref "MC1") (pin "1") (pinfunction "1_1") (pintype "passive"))
      (node (ref "MC1") (pin "3") (pinfunction "3_3") (pintype "passive"))
      (node (ref "MC1") (pin "5") (pinfunction "5_5") (pintype "passive"))
      (node (ref "R1") (pin "2") (pinfunction "2_2") (pintype "passive"))
      (node (ref "R2") (pin "2") (pinfunction "2_2") (pintype "passive"))
      (node (ref "U1") (pin "3") (pinfunction "IN_3") (pintype "power_in"))
      (node (ref "U5") (pin "1") (pinfunction "IN_1") (pintype "input"))
      (node (ref "U5") (pin "15") (pinfunction "CP_EN_15") (pintype "input"))
      (node (ref "U5") (pin "2") (pinfunction "IN_2") (pintype "input"))
      (node (ref "U5") (pin "3") (pinfunction "IN_3") (pintype "input"))
      (node (ref "U5") (pin "4") (pinfunction "IN_4") (pintype "input"))
      (node (ref "U_LS2") (pin "5") (pinfunction "VCC_5") (pintype "power_in"))
      (node (ref "VDCIN_CONN") (pin "1") (pinfunction "1_1") (pintype "passive"))
    )
    (net (code "6") (name "/+1.2V_PG") (class "Default")
      (node (ref "Q1") (pin "1") (pinfunction "B_1") (pintype "passive"))
      (node (ref "R8") (pin "1") (pinfunction "1_1") (pintype "passive"))
      (node (ref "U5") (pin "14") (pinfunction "PG_14") (pintype "output"))
    )
    (net (code "7") (name "/+VCCBATT") (class "Default")
      (node (ref "MC2") (pin "3") (pinfunction "3_3") (pintype "passive"))
    )
    (net (code "8") (name "/AVDD_EN") (class "Default")
      (node (ref "MC1") (pin "46") (pinfunction "46_46") (pintype "passive"))
      (node (ref "R27") (pin "2") (pinfunction "2_2") (pintype "passive"))
    )
    (net (code "9") (name "/AVDD_EN_toConn") (class "Default")
      (node (ref "J_ESHF") (pin "37") (pinfunction "37_37") (pintype "passive"))
      (node (ref "R27") (pin "1") (pinfunction "1_1") (pintype "passive"))
    )
    (net (code "10") (name "/CLKQUAD_CP_RSTB") (class "Default")
      (node (ref "MC1") (pin "16") (pinfunction "16_16") (pintype "passive"))
      (node (ref "U2") (pin "12") (pinfunction "B1_12") (pintype "bidirectional"))
    )
    (net (code "11") (name "/CLKQUAD_CP_RSTB_A") (class "Default")
      (node (ref "R12") (pin "1") (pinfunction "1_1") (pintype "passive"))
      (node (ref "U2") (pin "1") (pinfunction "A1_1") (pintype "bidirectional"))
    )
    (net (code "12") (name "/CLKQUAD_SCAN_CLK") (class "Default")
      (node (ref "MC1") (pin "28") (pinfunction "28_28") (pintype "passive"))
      (node (ref "U2") (pin "9") (pinfunction "B4_9") (pintype "bidirectional"))
    )
    (net (code "13") (name "/CLKQUAD_SCAN_CLK_A") (class "Default")
      (node (ref "R30") (pin "1") (pinfunction "1_1") (pintype "passive"))
      (node (ref "U2") (pin "4") (pinfunction "A4_4") (pintype "bidirectional"))
    )
    (net (code "14") (name "/CLKQUAD_SCAN_EN") (class "Default")
      (node (ref "MC1") (pin "20") (pinfunction "20_20") (pintype "passive"))
      (node (ref "U2") (pin "11") (pinfunction "B2_11") (pintype "bidirectional"))
    )
    (net (code "15") (name "/CLKQUAD_SCAN_EN_A") (class "Default")
      (node (ref "R19") (pin "1") (pinfunction "1_1") (pintype "passive"))
      (node (ref "U2") (pin "2") (pinfunction "A2_2") (pintype "bidirectional"))
    )
    (net (code "16") (name "/CLKQUAD_SCAN_IN") (class "Default")
      (node (ref "MC1") (pin "32") (pinfunction "32_32") (pintype "passive"))
      (node (ref "U4") (pin "5") (pinfunction "B1_5") (pintype "bidirectional"))
    )
    (net (code "17") (name "/CLKQUAD_SCAN_IN_A") (class "Default")
      (node (ref "R31") (pin "1") (pinfunction "1_1") (pintype "passive"))
      (node (ref "U4") (pin "8") (pinfunction "A1_8") (pintype "bidirectional"))
    )
    (net (code "18") (name "/CLKQUAD_SCAN_OUT") (class "Default")
      (node (ref "MC1") (pin "38") (pinfunction "38_38") (pintype "passive"))
      (node (ref "U4") (pin "4") (pinfunction "B2_4") (pintype "bidirectional"))
    )
    (net (code "19") (name "/CLKQUAD_SCAN_OUT_A") (class "Default")
      (node (ref "J_CLKQUAD") (pin "11") (pinfunction "11_11") (pintype "passive"))
      (node (ref "U4") (pin "9") (pinfunction "A2_9") (pintype "bidirectional"))
    )
    (net (code "20") (name "/CLKQUAD_SCAN_RST") (class "Default")
      (node (ref "MC1") (pin "24") (pinfunction "24_24") (pintype "passive"))
      (node (ref "U2") (pin "10") (pinfunction "B3_10") (pintype "bidirectional"))
    )
    (net (code "21") (name "/CLKQUAD_SCAN_RST_A") (class "Default")
      (node (ref "R26") (pin "1") (pinfunction "1_1") (pintype "passive"))
      (node (ref "U2") (pin "3") (pinfunction "A3_3") (pintype "bidirectional"))
    )
    (net (code "22") (name "/CLK_ENB") (class "Default")
      (node (ref "MC2") (pin "43") (pinfunction "43_43") (pintype "passive"))
      (node (ref "R25") (pin "2") (pinfunction "2_2") (pintype "passive"))
    )
    (net (code "23") (name "/CLK_ENB_toConn") (class "Default")
      (node (ref "J_ESHF") (pin "33") (pinfunction "33_33") (pintype "passive"))
      (node (ref "R25") (pin "1") (pinfunction "1_1") (pintype "passive"))
    )
    (net (code "24") (name "/CVDD_EN") (class "Default")
      (node (ref "MC1") (pin "50") (pinfunction "50_50") (pintype "passive"))
      (node (ref "R28") (pin "2") (pinfunction "2_2") (pintype "passive"))
    )
    (net (code "25") (name "/CVDD_EN_toConn") (class "Default")
      (node (ref "J_ESHF") (pin "39") (pinfunction "39_39") (pintype "passive"))
      (node (ref "R28") (pin "1") (pinfunction "1_1") (pintype "passive"))
    )
    (net (code "26") (name "/DESER_EN") (class "Default")
      (node (ref "MC2") (pin "42") (pinfunction "42_42") (pintype "passive"))
      (node (ref "R24") (pin "2") (pinfunction "2_2") (pintype "passive"))
    )
    (net (code "27") (name "/DESER_EN_toConn") (class "Default")
      (node (ref "J_ESHF") (pin "31") (pinfunction "31_31") (pintype "passive"))
      (node (ref "R24") (pin "1") (pinfunction "1_1") (pintype "passive"))
    )
    (net (code "28") (name "/DVDD_EN") (class "Default")
      (node (ref "MC1") (pin "54") (pinfunction "54_54") (pintype "passive"))
      (node (ref "R29") (pin "2") (pinfunction "2_2") (pintype "passive"))
    )
    (net (code "29") (name "/DVDD_EN_toConn") (class "Default")
      (node (ref "J_ESHF") (pin "41") (pinfunction "41_41") (pintype "passive"))
      (node (ref "R29") (pin "1") (pinfunction "1_1") (pintype "passive"))
    )
    (net (code "30") (name "/FPGA_JTAG_TCK") (class "Default")
      (node (ref "J_JTAG") (pin "6") (pinfunction "6_6") (pintype "passive"))
      (node (ref "MC2") (pin "5") (pinfunction "5_5") (pintype "passive"))
    )
    (net (code "31") (name "/FPGA_JTAG_TDI") (class "Default")
      (node (ref "J_JTAG") (pin "10") (pinfunction "10_10") (pintype "passive"))
      (node (ref "MC2") (pin "9") (pinfunction "9_9") (pintype "passive"))
    )
    (net (code "32") (name "/FPGA_JTAG_TDO") (class "Default")
      (node (ref "J_JTAG") (pin "8") (pinfunction "8_8") (pintype "passive"))
      (node (ref "MC2") (pin "8") (pinfunction "8_8") (pintype "passive"))
    )
    (net (code "33") (name "/FPGA_JTAG_TMS") (class "Default")
      (node (ref "J_JTAG") (pin "4") (pinfunction "4_4") (pintype "passive"))
      (node (ref "MC2") (pin "7") (pinfunction "7_7") (pintype "passive"))
    )
    (net (code "34") (name "/MC1_15") (class "Default")
      (node (ref "MC1") (pin "15") (pinfunction "15_15") (pintype "passive"))
    )
    (net (code "35") (name "/MC1_17") (class "Default")
      (node (ref "MC1") (pin "17") (pinfunction "17_17") (pintype "passive"))
    )
    (net (code "36") (name "/MC1_19") (class "Default")
      (node (ref "MC1") (pin "19") (pinfunction "19_19") (pintype "passive"))
    )
    (net (code "37") (name "/MC1_21") (class "Default")
      (node (ref "MC1") (pin "21") (pinfunction "21_21") (pintype "passive"))
    )
    (net (code "38") (name "/MC1_23") (class "Default")
      (node (ref "MC1") (pin "23") (pinfunction "23_23") (pintype "passive"))
    )
    (net (code "39") (name "/MC1_25") (class "Default")
      (node (ref "MC1") (pin "25") (pinfunction "25_25") (pintype "passive"))
    )
    (net (code "40") (name "/MC1_27") (class "Default")
      (node (ref "MC1") (pin "27") (pinfunction "27_27") (pintype "passive"))
    )
    (net (code "41") (name "/MC1_29") (class "Default")
      (node (ref "MC1") (pin "29") (pinfunction "29_29") (pintype "passive"))
    )
    (net (code "42") (name "/MC1_31") (class "Default")
      (node (ref "MC1") (pin "31") (pinfunction "31_31") (pintype "passive"))
    )
    (net (code "43") (name "/MC1_33") (class "Default")
      (node (ref "MC1") (pin "33") (pinfunction "33_33") (pintype "passive"))
    )
    (net (code "44") (name "/MC1_37") (class "Default")
      (node (ref "MC1") (pin "37") (pinfunction "37_37") (pintype "passive"))
    )
    (net (code "45") (name "/MC1_39") (class "Default")
      (node (ref "MC1") (pin "39") (pinfunction "39_39") (pintype "passive"))
    )
    (net (code "46") (name "/MC1_40") (class "Default")
      (node (ref "MC1") (pin "40") (pinfunction "40_40") (pintype "passive"))
    )
    (net (code "47") (name "/MC1_41") (class "Default")
      (node (ref "MC1") (pin "41") (pinfunction "41_41") (pintype "passive"))
    )
    (net (code "48") (name "/MC1_43") (class "Default")
      (node (ref "MC1") (pin "43") (pinfunction "43_43") (pintype "passive"))
    )
    (net (code "49") (name "/MC1_44") (class "Default")
      (node (ref "MC1") (pin "44") (pinfunction "44_44") (pintype "passive"))
    )
    (net (code "50") (name "/MC1_45") (class "Default")
      (node (ref "MC1") (pin "45") (pinfunction "45_45") (pintype "passive"))
    )
    (net (code "51") (name "/MC1_47") (class "Default")
      (node (ref "MC1") (pin "47") (pinfunction "47_47") (pintype "passive"))
    )
    (net (code "52") (name "/MC1_48") (class "Default")
      (node (ref "MC1") (pin "48") (pinfunction "48_48") (pintype "passive"))
    )
    (net (code "53") (name "/MC1_49") (class "Default")
      (node (ref "MC1") (pin "49") (pinfunction "49_49") (pintype "passive"))
    )
    (net (code "54") (name "/MC1_51") (class "Default")
      (node (ref "MC1") (pin "51") (pinfunction "51_51") (pintype "passive"))
    )
    (net (code "55") (name "/MC1_52") (class "Default")
      (node (ref "MC1") (pin "52") (pinfunction "52_52") (pintype "passive"))
    )
    (net (code "56") (name "/MC1_53") (class "Default")
      (node (ref "MC1") (pin "53") (pinfunction "53_53") (pintype "passive"))
    )
    (net (code "57") (name "/MC1_57") (class "Default")
      (node (ref "MC1") (pin "57") (pinfunction "57_57") (pintype "passive"))
    )
    (net (code "58") (name "/MC1_58") (class "Default")
      (node (ref "MC1") (pin "58") (pinfunction "58_58") (pintype "passive"))
    )
    (net (code "59") (name "/MC1_59") (class "Default")
      (node (ref "MC1") (pin "59") (pinfunction "59_59") (pintype "passive"))
    )
    (net (code "60") (name "/MC1_60") (class "Default")
      (node (ref "MC1") (pin "60") (pinfunction "60_60") (pintype "passive"))
    )
    (net (code "61") (name "/MC1_61") (class "Default")
      (node (ref "MC1") (pin "61") (pinfunction "61_61") (pintype "passive"))
    )
    (net (code "62") (name "/MC1_62") (class "Default")
      (node (ref "MC1") (pin "62") (pinfunction "62_62") (pintype "passive"))
    )
    (net (code "63") (name "/MC1_63") (class "Default")
      (node (ref "MC1") (pin "63") (pinfunction "63_63") (pintype "passive"))
    )
    (net (code "64") (name "/MC1_64") (class "Default")
      (node (ref "MC1") (pin "64") (pinfunction "64_64") (pintype "passive"))
    )
    (net (code "65") (name "/MC1_65") (class "Default")
      (node (ref "MC1") (pin "65") (pinfunction "65_65") (pintype "passive"))
    )
    (net (code "66") (name "/MC1_66") (class "Default")
      (node (ref "MC1") (pin "66") (pinfunction "66_66") (pintype "passive"))
    )
    (net (code "67") (name "/MC1_67") (class "Default")
      (node (ref "MC1") (pin "67") (pinfunction "67_67") (pintype "passive"))
    )
    (net (code "68") (name "/MC1_68") (class "Default")
      (node (ref "MC1") (pin "68") (pinfunction "68_68") (pintype "passive"))
    )
    (net (code "69") (name "/MC1_69") (class "Default")
      (node (ref "MC1") (pin "69") (pinfunction "69_69") (pintype "passive"))
    )
    (net (code "70") (name "/MC1_70") (class "Default")
      (node (ref "MC1") (pin "70") (pinfunction "70_70") (pintype "passive"))
    )
    (net (code "71") (name "/MC1_71") (class "Default")
      (node (ref "MC1") (pin "71") (pinfunction "71_71") (pintype "passive"))
    )
    (net (code "72") (name "/MC1_72") (class "Default")
      (node (ref "MC1") (pin "72") (pinfunction "72_72") (pintype "passive"))
    )
    (net (code "73") (name "/MC1_73") (class "Default")
      (node (ref "MC1") (pin "73") (pinfunction "73_73") (pintype "passive"))
    )
    (net (code "74") (name "/MC1_74") (class "Default")
      (node (ref "MC1") (pin "74") (pinfunction "74_74") (pintype "passive"))
    )
    (net (code "75") (name "/MC1_75") (class "Default")
      (node (ref "MC1") (pin "75") (pinfunction "75_75") (pintype "passive"))
    )
    (net (code "76") (name "/MC1_76") (class "Default")
      (node (ref "MC1") (pin "76") (pinfunction "76_76") (pintype "passive"))
    )
    (net (code "77") (name "/MC1_77") (class "Default")
      (node (ref "MC1") (pin "77") (pinfunction "77_77") (pintype "passive"))
    )
    (net (code "78") (name "/MC1_79") (class "Default")
      (node (ref "MC1") (pin "79") (pinfunction "79_79") (pintype "passive"))
    )
    (net (code "79") (name "/MC2_10") (class "Default")
      (node (ref "MC2") (pin "10") (pinfunction "10_10") (pintype "passive"))
    )
    (net (code "80") (name "/MC2_12") (class "Default")
      (node (ref "MC2") (pin "12") (pinfunction "12_12") (pintype "passive"))
    )
    (net (code "81") (name "/MC2_15") (class "Default")
      (node (ref "MC2") (pin "15") (pinfunction "15_15") (pintype "passive"))
    )
    (net (code "82") (name "/MC2_18") (class "Default")
      (node (ref "MC2") (pin "18") (pinfunction "18_18") (pintype "passive"))
    )
    (net (code "83") (name "/MC2_19") (class "Default")
      (node (ref "MC2") (pin "19") (pinfunction "19_19") (pintype "passive"))
    )
    (net (code "84") (name "/MC2_22") (class "Default")
      (node (ref "MC2") (pin "22") (pinfunction "22_22") (pintype "passive"))
    )
    (net (code "85") (name "/MC2_23") (class "Default")
      (node (ref "MC2") (pin "23") (pinfunction "23_23") (pintype "passive"))
    )
    (net (code "86") (name "/MC2_26") (class "Default")
      (node (ref "MC2") (pin "26") (pinfunction "26_26") (pintype "passive"))
    )
    (net (code "87") (name "/MC2_27") (class "Default")
      (node (ref "MC2") (pin "27") (pinfunction "27_27") (pintype "passive"))
    )
    (net (code "88") (name "/MC2_30") (class "Default")
      (node (ref "MC2") (pin "30") (pinfunction "30_30") (pintype "passive"))
    )
    (net (code "89") (name "/MC2_31") (class "Default")
      (node (ref "MC2") (pin "31") (pinfunction "31_31") (pintype "passive"))
    )
    (net (code "90") (name "/MC2_34") (class "Default")
      (node (ref "MC2") (pin "34") (pinfunction "34_34") (pintype "passive"))
    )
    (net (code "91") (name "/MC2_37") (class "Default")
      (node (ref "MC2") (pin "37") (pinfunction "37_37") (pintype "passive"))
    )
    (net (code "92") (name "/MC2_40") (class "Default")
      (node (ref "MC2") (pin "40") (pinfunction "40_40") (pintype "passive"))
    )
    (net (code "93") (name "/MC2_41") (class "Default")
      (node (ref "MC2") (pin "41") (pinfunction "41_41") (pintype "passive"))
    )
    (net (code "94") (name "/MC2_45") (class "Default")
      (node (ref "MC2") (pin "45") (pinfunction "45_45") (pintype "passive"))
    )
    (net (code "95") (name "/MC2_46") (class "Default")
      (node (ref "MC2") (pin "46") (pinfunction "46_46") (pintype "passive"))
    )
    (net (code "96") (name "/MC2_47") (class "Default")
      (node (ref "MC2") (pin "47") (pinfunction "47_47") (pintype "passive"))
    )
    (net (code "97") (name "/MC2_48") (class "Default")
      (node (ref "MC2") (pin "48") (pinfunction "48_48") (pintype "passive"))
    )
    (net (code "98") (name "/MC2_49") (class "Default")
      (node (ref "MC2") (pin "49") (pinfunction "49_49") (pintype "passive"))
    )
    (net (code "99") (name "/MC2_50") (class "Default")
      (node (ref "MC2") (pin "50") (pinfunction "50_50") (pintype "passive"))
    )
    (net (code "100") (name "/MC2_51") (class "Default")
      (node (ref "MC2") (pin "51") (pinfunction "51_51") (pintype "passive"))
    )
    (net (code "101") (name "/MC2_52") (class "Default")
      (node (ref "MC2") (pin "52") (pinfunction "52_52") (pintype "passive"))
    )
    (net (code "102") (name "/MC2_53") (class "Default")
      (node (ref "MC2") (pin "53") (pinfunction "53_53") (pintype "passive"))
    )
    (net (code "103") (name "/MC2_54") (class "Default")
      (node (ref "MC2") (pin "54") (pinfunction "54_54") (pintype "passive"))
    )
    (net (code "104") (name "/MC2_57") (class "Default")
      (node (ref "MC2") (pin "57") (pinfunction "57_57") (pintype "passive"))
    )
    (net (code "105") (name "/MC2_60") (class "Default")
      (node (ref "MC2") (pin "60") (pinfunction "60_60") (pintype "passive"))
    )
    (net (code "106") (name "/MC2_61") (class "Default")
      (node (ref "MC2") (pin "61") (pinfunction "61_61") (pintype "passive"))
    )
    (net (code "107") (name "/MC2_63") (class "Default")
      (node (ref "MC2") (pin "63") (pinfunction "63_63") (pintype "passive"))
    )
    (net (code "108") (name "/MC2_64") (class "Default")
      (node (ref "MC2") (pin "64") (pinfunction "64_64") (pintype "passive"))
    )
    (net (code "109") (name "/MC2_66") (class "Default")
      (node (ref "MC2") (pin "66") (pinfunction "66_66") (pintype "passive"))
    )
    (net (code "110") (name "/MC2_67") (class "Default")
      (node (ref "MC2") (pin "67") (pinfunction "67_67") (pintype "passive"))
    )
    (net (code "111") (name "/MC2_68") (class "Default")
      (node (ref "MC2") (pin "68") (pinfunction "68_68") (pintype "passive"))
    )
    (net (code "112") (name "/MC2_69") (class "Default")
      (node (ref "MC2") (pin "69") (pinfunction "69_69") (pintype "passive"))
    )
    (net (code "113") (name "/MC2_70") (class "Default")
      (node (ref "MC2") (pin "70") (pinfunction "70_70") (pintype "passive"))
    )
    (net (code "114") (name "/MC2_71") (class "Default")
      (node (ref "MC2") (pin "71") (pinfunction "71_71") (pintype "passive"))
    )
    (net (code "115") (name "/MC2_72") (class "Default")
      (node (ref "MC2") (pin "72") (pinfunction "72_72") (pintype "passive"))
    )
    (net (code "116") (name "/MC2_73") (class "Default")
      (node (ref "MC2") (pin "73") (pinfunction "73_73") (pintype "passive"))
    )
    (net (code "117") (name "/MC2_74") (class "Default")
      (node (ref "MC2") (pin "74") (pinfunction "74_74") (pintype "passive"))
    )
    (net (code "118") (name "/MC2_75") (class "Default")
      (node (ref "MC2") (pin "75") (pinfunction "75_75") (pintype "passive"))
    )
    (net (code "119") (name "/MC2_76") (class "Default")
      (node (ref "MC2") (pin "76") (pinfunction "76_76") (pintype "passive"))
    )
    (net (code "120") (name "/MC2_79") (class "Default")
      (node (ref "MC2") (pin "79") (pinfunction "79_79") (pintype "passive"))
    )
    (net (code "121") (name "/MEM_CLK") (class "Default")
      (node (ref "J_MEM_CLK") (pin "1") (pinfunction "Signal_1") (pintype "input"))
      (node (ref "MC2") (pin "65") (pinfunction "65_65") (pintype "passive"))
    )
    (net (code "122") (name "/MEM_DATA") (class "Default")
      (node (ref "J_MEM_DATA") (pin "1") (pinfunction "Signal_1") (pintype "input"))
      (node (ref "MC2") (pin "77") (pinfunction "77_77") (pintype "passive"))
    )
    (net (code "123") (name "/PMBus_ALERT") (class "Default")
      (node (ref "MC2") (pin "59") (pinfunction "59_59") (pintype "passive"))
    )
    (net (code "124") (name "/SCAN_ANA_CLK") (class "Default")
      (node (ref "MC2") (pin "16") (pinfunction "16_16") (pintype "passive"))
      (node (ref "R4") (pin "2") (pinfunction "2_2") (pintype "passive"))
    )
    (net (code "125") (name "/SCAN_ANA_EN") (class "Default")
      (node (ref "MC2") (pin "17") (pinfunction "17_17") (pintype "passive"))
      (node (ref "R5") (pin "2") (pinfunction "2_2") (pintype "passive"))
    )
    (net (code "126") (name "/SCAN_ANA_IN") (class "Default")
      (node (ref "MC2") (pin "20") (pinfunction "20_20") (pintype "passive"))
      (node (ref "R6") (pin "2") (pinfunction "2_2") (pintype "passive"))
    )
    (net (code "127") (name "/SCAN_ANA_OUT") (class "Default")
      (node (ref "J_ESHF") (pin "15") (pinfunction "15_15") (pintype "passive"))
      (node (ref "MC2") (pin "24") (pinfunction "24_24") (pintype "passive"))
    )
    (net (code "128") (name "/SCAN_ANA_RST") (class "Default")
      (node (ref "MC2") (pin "21") (pinfunction "21_21") (pintype "passive"))
      (node (ref "R11") (pin "2") (pinfunction "2_2") (pintype "passive"))
    )
    (net (code "129") (name "/SCAN_A_CLK") (class "Default")
      (node (ref "J_ESHF") (pin "7") (pinfunction "7_7") (pintype "passive"))
      (node (ref "R4") (pin "1") (pinfunction "1_1") (pintype "passive"))
    )
    (net (code "130") (name "/SCAN_A_EN") (class "Default")
      (node (ref "J_ESHF") (pin "9") (pinfunction "9_9") (pintype "passive"))
      (node (ref "R5") (pin "1") (pinfunction "1_1") (pintype "passive"))
    )
    (net (code "131") (name "/SCAN_A_IN") (class "Default")
      (node (ref "J_ESHF") (pin "11") (pinfunction "11_11") (pintype "passive"))
      (node (ref "R6") (pin "1") (pinfunction "1_1") (pintype "passive"))
    )
    (net (code "132") (name "/SCAN_A_RST") (class "Default")
      (node (ref "J_ESHF") (pin "13") (pinfunction "13_13") (pintype "passive"))
      (node (ref "R11") (pin "1") (pinfunction "1_1") (pintype "passive"))
    )
    (net (code "133") (name "/SCAN_DIG_CLKN") (class "Default")
      (node (ref "MC2") (pin "28") (pinfunction "28_28") (pintype "passive"))
      (node (ref "R14") (pin "2") (pinfunction "2_2") (pintype "passive"))
    )
    (net (code "134") (name "/SCAN_DIG_CLKP") (class "Default")
      (node (ref "MC2") (pin "29") (pinfunction "29_29") (pintype "passive"))
      (node (ref "R15") (pin "2") (pinfunction "2_2") (pintype "passive"))
    )
    (net (code "135") (name "/SCAN_DIG_EN") (class "Default")
      (node (ref "MC2") (pin "33") (pinfunction "33_33") (pintype "passive"))
      (node (ref "R17") (pin "2") (pinfunction "2_2") (pintype "passive"))
    )
    (net (code "136") (name "/SCAN_DIG_IN") (class "Default")
      (node (ref "MC2") (pin "25") (pinfunction "25_25") (pintype "passive"))
      (node (ref "R13") (pin "2") (pinfunction "2_2") (pintype "passive"))
    )
    (net (code "137") (name "/SCAN_DIG_OUT") (class "Default")
      (node (ref "J_ESHF") (pin "29") (pinfunction "29_29") (pintype "passive"))
      (node (ref "MC2") (pin "39") (pinfunction "39_39") (pintype "passive"))
    )
    (net (code "138") (name "/SCAN_DIG_RST") (class "Default")
      (node (ref "MC2") (pin "32") (pinfunction "32_32") (pintype "passive"))
      (node (ref "R16") (pin "2") (pinfunction "2_2") (pintype "passive"))
    )
    (net (code "139") (name "/SCAN_DIG_UPDATE") (class "Default")
      (node (ref "MC2") (pin "38") (pinfunction "38_38") (pintype "passive"))
      (node (ref "R18") (pin "2") (pinfunction "2_2") (pintype "passive"))
    )
    (net (code "140") (name "/SCAN_D_CLKN") (class "Default")
      (node (ref "J_ESHF") (pin "19") (pinfunction "19_19") (pintype "passive"))
      (node (ref "R14") (pin "1") (pinfunction "1_1") (pintype "passive"))
    )
    (net (code "141") (name "/SCAN_D_CLKP") (class "Default")
      (node (ref "J_ESHF") (pin "21") (pinfunction "21_21") (pintype "passive"))
      (node (ref "R15") (pin "1") (pinfunction "1_1") (pintype "passive"))
    )
    (net (code "142") (name "/SCAN_D_EN") (class "Default")
      (node (ref "J_ESHF") (pin "25") (pinfunction "25_25") (pintype "passive"))
      (node (ref "R17") (pin "1") (pinfunction "1_1") (pintype "passive"))
    )
    (net (code "143") (name "/SCAN_D_IN") (class "Default")
      (node (ref "J_ESHF") (pin "17") (pinfunction "17_17") (pintype "passive"))
      (node (ref "R13") (pin "1") (pinfunction "1_1") (pintype "passive"))
    )
    (net (code "144") (name "/SCAN_D_RST") (class "Default")
      (node (ref "J_ESHF") (pin "23") (pinfunction "23_23") (pintype "passive"))
      (node (ref "R16") (pin "1") (pinfunction "1_1") (pintype "passive"))
    )
    (net (code "145") (name "/SCAN_D_UPDATE") (class "Default")
      (node (ref "J_ESHF") (pin "27") (pinfunction "27_27") (pintype "passive"))
      (node (ref "R18") (pin "1") (pinfunction "1_1") (pintype "passive"))
    )
    (net (code "146") (name "/SCL_Conn") (class "Default")
      (node (ref "J_ESHF") (pin "47") (pinfunction "47_47") (pintype "passive"))
      (node (ref "R_SCL") (pin "2") (pinfunction "2_2") (pintype "passive"))
    )
    (net (code "147") (name "/SCL_JUMPER") (class "Default")
      (node (ref "J_SCL2") (pin "1") (pinfunction "1_1") (pintype "passive"))
      (node (ref "R_SCL") (pin "1") (pinfunction "1_1") (pintype "passive"))
    )
    (net (code "148") (name "/SCL_MCP2221A") (class "Default")
      (node (ref "J_QWIIC") (pin "1") (pinfunction "1_1") (pintype "passive"))
      (node (ref "J_SCL2") (pin "2") (pinfunction "2_2") (pintype "passive"))
      (node (ref "R22") (pin "1") (pinfunction "1_1") (pintype "passive"))
      (node (ref "U3") (pin "10") (pinfunction "SCL_10") (pintype "input"))
    )
    (net (code "149") (name "/SDA_Conn") (class "Default")
      (node (ref "J_ESHF") (pin "45") (pinfunction "45_45") (pintype "passive"))
      (node (ref "R_SDA") (pin "2") (pinfunction "2_2") (pintype "passive"))
    )
    (net (code "150") (name "/SDA_JUMPER") (class "Default")
      (node (ref "J_SDA2") (pin "1") (pinfunction "1_1") (pintype "passive"))
      (node (ref "R_SDA") (pin "1") (pinfunction "1_1") (pintype "passive"))
    )
    (net (code "151") (name "/SDA_MCP2221A") (class "Default")
      (node (ref "J_QWIIC") (pin "2") (pinfunction "2_2") (pintype "passive"))
      (node (ref "J_SDA2") (pin "2") (pinfunction "2_2") (pintype "passive"))
      (node (ref "R23") (pin "1") (pinfunction "1_1") (pintype "passive"))
      (node (ref "U3") (pin "9") (pinfunction "SDA_9") (pintype "bidirectional"))
    )
    (net (code "152") (name "/SYS_CLK_MC1") (class "Default")
      (node (ref "MC1") (pin "8") (pinfunction "8_8") (pintype "passive"))
    )
    (net (code "153") (name "/SYS_CLK_MC2") (class "Default")
      (node (ref "MC2") (pin "11") (pinfunction "11_11") (pintype "passive"))
    )
    (net (code "154") (name "/USB_D+") (class "Default")
      (node (ref "J_USB") (pin "3") (pinfunction "D+_3") (pintype "passive"))
      (node (ref "U3") (pin "13") (pinfunction "D+_13") (pintype "bidirectional"))
    )
    (net (code "155") (name "/USB_D-") (class "Default")
      (node (ref "J_USB") (pin "2") (pinfunction "D-_2") (pintype "passive"))
      (node (ref "U3") (pin "12") (pinfunction "D-_12") (pintype "bidirectional"))
    )
    (net (code "156") (name "/VBUS_P5V0") (class "Default")
      (node (ref "C12") (pin "1") (pinfunction "1_1") (pintype "passive"))
      (node (ref "C14") (pin "1") (pinfunction "1_1") (pintype "passive"))
      (node (ref "C15") (pin "1") (pinfunction "1_1") (pintype "passive"))
      (node (ref "J_USB") (pin "1") (pinfunction "VBUS_1") (pintype "passive"))
      (node (ref "U3") (pin "11") (pinfunction "VUSB_11") (pintype "power_in"))
    )
    (net (code "157") (name "/XADC_VN_FILT") (class "Default")
      (node (ref "MC1") (pin "10") (pinfunction "10_10") (pintype "passive+no_connect"))
    )
    (net (code "158") (name "/XADC_VP_FILT") (class "Default")
      (node (ref "MC1") (pin "12") (pinfunction "12_12") (pintype "passive+no_connect"))
    )
    (net (code "159") (name "/XEM7310_PG_5V5") (class "Default")
      (node (ref "R7") (pin "2") (pinfunction "2_2") (pintype "passive"))
      (node (ref "U_LS2") (pin "4") (pinfunction "Y_4") (pintype "output"))
    )
    (net (code "160") (name "GND") (class "Default")
      (node (ref "C1") (pin "2") (pinfunction "2_2") (pintype "passive"))
      (node (ref "C10") (pin "2") (pinfunction "2_2") (pintype "passive"))
      (node (ref "C11") (pin "2") (pinfunction "2_2") (pintype "passive"))
      (node (ref "C12") (pin "2") (pinfunction "2_2") (pintype "passive"))
      (node (ref "C13") (pin "2") (pinfunction "2_2") (pintype "passive"))
      (node (ref "C14") (pin "2") (pinfunction "2_2") (pintype "passive"))
      (node (ref "C15") (pin "2") (pinfunction "2_2") (pintype "passive"))
      (node (ref "C16") (pin "2") (pinfunction "2_2") (pintype "passive"))
      (node (ref "C17") (pin "2") (pinfunction "2_2") (pintype "passive"))
      (node (ref "C18") (pin "2") (pinfunction "2_2") (pintype "passive"))
      (node (ref "C19") (pin "2") (pinfunction "2_2") (pintype "passive"))
      (node (ref "C2") (pin "2") (pinfunction "2_2") (pintype "passive"))
      (node (ref "C20") (pin "2") (pinfunction "2_2") (pintype "passive"))
      (node (ref "C3") (pin "1") (pinfunction "1_1") (pintype "passive"))
      (node (ref "C4") (pin "2") (pinfunction "2_2") (pintype "passive"))
      (node (ref "C5") (pin "2") (pinfunction "2_2") (pintype "passive"))
      (node (ref "C6") (pin "2") (pinfunction "2_2") (pintype "passive"))
      (node (ref "C7") (pin "2") (pinfunction "2_2") (pintype "passive"))
      (node (ref "C8") (pin "2") (pinfunction "2_2") (pintype "passive"))
      (node (ref "C9") (pin "1") (pinfunction "C_1") (pintype "passive"))
      (node (ref "D3") (pin "2") (pinfunction "A2_2") (pintype "passive"))
      (node (ref "D_5V5") (pin "1") (pinfunction "C_1") (pintype "passive"))
      (node (ref "GND_CONN") (pin "1") (pinfunction "1_1") (pintype "passive"))
      (node (ref "J_CLKQUAD") (pin "02") (pinfunction "02_02") (pintype "passive"))
      (node (ref "J_CLKQUAD") (pin "04") (pinfunction "04_04") (pintype "passive"))
      (node (ref "J_CLKQUAD") (pin "06") (pinfunction "06_06") (pintype "passive"))
      (node (ref "J_CLKQUAD") (pin "08") (pinfunction "08_08") (pintype "passive"))
      (node (ref "J_CLKQUAD") (pin "10") (pinfunction "10_10") (pintype "passive"))
      (node (ref "J_CLKQUAD") (pin "12") (pinfunction "12_12") (pintype "passive"))
      (node (ref "J_CLKQUAD") (pin "13") (pinfunction "13_13") (pintype "passive"))
      (node (ref "J_CLKQUAD") (pin "14") (pinfunction "14_14") (pintype "passive"))
      (node (ref "J_ESHF") (pin "1") (pinfunction "1_1") (pintype "passive"))
      (node (ref "J_ESHF") (pin "10") (pinfunction "10_10") (pintype "passive"))
      (node (ref "J_ESHF") (pin "12") (pinfunction "12_12") (pintype "passive"))
      (node (ref "J_ESHF") (pin "14") (pinfunction "14_14") (pintype "passive"))
      (node (ref "J_ESHF") (pin "16") (pinfunction "16_16") (pintype "passive"))
      (node (ref "J_ESHF") (pin "18") (pinfunction "18_18") (pintype "passive"))
      (node (ref "J_ESHF") (pin "2") (pinfunction "2_2") (pintype "passive"))
      (node (ref "J_ESHF") (pin "20") (pinfunction "20_20") (pintype "passive"))
      (node (ref "J_ESHF") (pin "22") (pinfunction "22_22") (pintype "passive"))
      (node (ref "J_ESHF") (pin "24") (pinfunction "24_24") (pintype "passive"))
      (node (ref "J_ESHF") (pin "26") (pinfunction "26_26") (pintype "passive"))
      (node (ref "J_ESHF") (pin "28") (pinfunction "28_28") (pintype "passive"))
      (node (ref "J_ESHF") (pin "3") (pinfunction "3_3") (pintype "passive"))
      (node (ref "J_ESHF") (pin "30") (pinfunction "30_30") (pintype "passive"))
      (node (ref "J_ESHF") (pin "32") (pinfunction "32_32") (pintype "passive"))
      (node (ref "J_ESHF") (pin "34") (pinfunction "34_34") (pintype "passive"))
      (node (ref "J_ESHF") (pin "35") (pinfunction "35_35") (pintype "passive"))
      (node (ref "J_ESHF") (pin "36") (pinfunction "36_36") (pintype "passive"))
      (node (ref "J_ESHF") (pin "38") (pinfunction "38_38") (pintype "passive"))
      (node (ref "J_ESHF") (pin "4") (pinfunction "4_4") (pintype "passive"))
      (node (ref "J_ESHF") (pin "40") (pinfunction "40_40") (pintype "passive"))
      (node (ref "J_ESHF") (pin "42") (pinfunction "42_42") (pintype "passive"))
      (node (ref "J_ESHF") (pin "44") (pinfunction "44_44") (pintype "passive"))
      (node (ref "J_ESHF") (pin "46") (pinfunction "46_46") (pintype "passive"))
      (node (ref "J_ESHF") (pin "48") (pinfunction "48_48") (pintype "passive"))
      (node (ref "J_ESHF") (pin "49") (pinfunction "49_49") (pintype "passive"))
      (node (ref "J_ESHF") (pin "5") (pinfunction "5_5") (pintype "passive"))
      (node (ref "J_ESHF") (pin "50") (pinfunction "50_50") (pintype "passive"))
      (node (ref "J_ESHF") (pin "6") (pinfunction "6_6") (pintype "passive"))
      (node (ref "J_ESHF") (pin "8") (pinfunction "8_8") (pintype "passive"))
      (node (ref "J_GND1") (pin "1") (pinfunction "1_1") (pintype "passive"))
      (node (ref "J_GND2") (pin "1") (pinfunction "1_1") (pintype "passive"))
      (node (ref "J_GND3") (pin "1") (pinfunction "1_1") (pintype "passive"))
      (node (ref "J_GND4") (pin "1") (pinfunction "1_1") (pintype "passive"))
      (node (ref "J_JACK") (pin "2") (pinfunction "2_2") (pintype "passive"))
      (node (ref "J_JACK") (pin "3") (pinfunction "3_3") (pintype "passive"))
      (node (ref "J_JTAG") (pin "1") (pinfunction "1_1") (pintype "passive"))
      (node (ref "J_JTAG") (pin "11") (pinfunction "11_11") (pintype "passive"))
      (node (ref "J_JTAG") (pin "13") (pinfunction "13_13") (pintype "passive"))
      (node (ref "J_JTAG") (pin "3") (pinfunction "3_3") (pintype "passive"))
      (node (ref "J_JTAG") (pin "5") (pinfunction "5_5") (pintype "passive"))
      (node (ref "J_JTAG") (pin "7") (pinfunction "7_7") (pintype "passive"))
      (node (ref "J_JTAG") (pin "9") (pinfunction "9_9") (pintype "passive"))
      (node (ref "J_MEM_CLK") (pin "2") (pinfunction "GND_2") (pintype "power_in"))
      (node (ref "J_MEM_CLK") (pin "3") (pinfunction "GND_3") (pintype "power_in"))
      (node (ref "J_MEM_CLK") (pin "4") (pinfunction "GND_4") (pintype "power_in"))
      (node (ref "J_MEM_CLK") (pin "5") (pinfunction "GND_5") (pintype "power_in"))
      (node (ref "J_MEM_DATA") (pin "2") (pinfunction "GND_2") (pintype "power_in"))
      (node (ref "J_MEM_DATA") (pin "3") (pinfunction "GND_3") (pintype "power_in"))
      (node (ref "J_MEM_DATA") (pin "4") (pinfunction "GND_4") (pintype "power_in"))
      (node (ref "J_MEM_DATA") (pin "5") (pinfunction "GND_5") (pintype "power_in"))
      (node (ref "J_QWIIC") (pin "4") (pinfunction "4_4") (pintype "passive"))
      (node (ref "J_QWIIC") (pin "SH1") (pinfunction "SHIELD_SH1") (pintype "passive"))
      (node (ref "J_QWIIC") (pin "SH2") (pinfunction "SHIELD_SH2") (pintype "passive"))
      (node (ref "J_USB") (pin "5") (pinfunction "GND_5") (pintype "passive"))
      (node (ref "J_USB") (pin "Shell") (pinfunction "Shield_Shell") (pintype "passive"))
      (node (ref "MC1") (pin "14") (pinfunction "14_14") (pintype "passive"))
      (node (ref "MC1") (pin "2") (pinfunction "2_2") (pintype "passive"))
      (node (ref "MC1") (pin "35") (pinfunction "35_35") (pintype "passive"))
      (node (ref "MC1") (pin "55") (pinfunction "55_55") (pintype "passive"))
      (node (ref "MC1") (pin "78") (pinfunction "78_78") (pintype "passive"))
      (node (ref "MC1") (pin "80") (pinfunction "80_80") (pintype "passive"))
      (node (ref "MC2") (pin "1") (pinfunction "1_1") (pintype "passive"))
      (node (ref "MC2") (pin "13") (pinfunction "13_13") (pintype "passive"))
      (node (ref "MC2") (pin "14") (pinfunction "14_14") (pintype "passive"))
      (node (ref "MC2") (pin "36") (pinfunction "36_36") (pintype "passive"))
      (node (ref "MC2") (pin "56") (pinfunction "56_56") (pintype "passive"))
      (node (ref "MC2") (pin "78") (pinfunction "78_78") (pintype "passive"))
      (node (ref "MC2") (pin "80") (pinfunction "80_80") (pintype "passive"))
      (node (ref "P1V2_EN") (pin "1") (pinfunction "1_1") (pintype "passive"))
      (node (ref "P1V2_POT") (pin "3") (pinfunction "CW_3") (pintype "passive"))
      (node (ref "Q1") (pin "2") (pinfunction "E_2") (pintype "passive"))
      (node (ref "R9") (pin "2") (pinfunction "2_2") (pintype "passive"))
      (node (ref "U1") (pin "1") (pinfunction "GND_1") (pintype "power_in"))
      (node (ref "U2") (pin "15") (pinfunction "DIR1_15") (pintype "input"))
      (node (ref "U2") (pin "16") (pinfunction "DIR2_16") (pintype "input"))
      (node (ref "U2") (pin "5") (pinfunction "DIR3_5") (pintype "input"))
      (node (ref "U2") (pin "6") (pinfunction "DIR4_6") (pintype "input"))
      (node (ref "U2") (pin "7") (pinfunction "~{OE}_7") (pintype "input"))
      (node (ref "U2") (pin "8") (pinfunction "GND_8") (pintype "power_in"))
      (node (ref "U3") (pin "14") (pinfunction "VSS_14") (pintype "power_in"))
      (node (ref "U4") (pin "10") (pinfunction "DIR1_10") (pintype "passive"))
      (node (ref "U4") (pin "2") (pinfunction "~{OE}_2") (pintype "output"))
      (node (ref "U4") (pin "3") (pinfunction "GND_3") (pintype "power_in"))
      (node (ref "U5") (pin "17") (pinfunction "PAD_17") (pintype "power_in"))
      (node (ref "U5") (pin "6") (pinfunction "GND_6") (pintype "power_in"))
      (node (ref "U_LS1") (pin "3") (pinfunction "GND_3") (pintype "power_in"))
      (node (ref "U_LS2") (pin "3") (pinfunction "GND_3") (pintype "power_in"))
    )
    (net (code "161") (name "Net-(D_1V2-A)") (class "Default")
      (node (ref "D_1V2") (pin "2") (pinfunction "A_2") (pintype "passive"))
      (node (ref "R1") (pin "1") (pinfunction "1_1") (pintype "passive"))
    )
    (net (code "162") (name "Net-(D_1V2-C)") (class "Default")
      (node (ref "D_1V2") (pin "1") (pinfunction "C_1") (pintype "passive"))
      (node (ref "Q1") (pin "3") (pinfunction "C_3") (pintype "passive"))
    )
    (net (code "163") (name "Net-(D_5V5-A)") (class "Default")
      (node (ref "D_5V5") (pin "2") (pinfunction "A_2") (pintype "passive"))
      (node (ref "R2") (pin "1") (pinfunction "1_1") (pintype "passive"))
    )
    (net (code "164") (name "Net-(J_CLKQUAD-Pad01)") (class "Default")
      (node (ref "J_CLKQUAD") (pin "01") (pinfunction "01_01") (pintype "passive"))
      (node (ref "R12") (pin "2") (pinfunction "2_2") (pintype "passive"))
    )
    (net (code "165") (name "Net-(J_CLKQUAD-Pad03)") (class "Default")
      (node (ref "J_CLKQUAD") (pin "03") (pinfunction "03_03") (pintype "passive"))
      (node (ref "R19") (pin "2") (pinfunction "2_2") (pintype "passive"))
    )
    (net (code "166") (name "Net-(J_CLKQUAD-Pad05)") (class "Default")
      (node (ref "J_CLKQUAD") (pin "05") (pinfunction "05_05") (pintype "passive"))
      (node (ref "R26") (pin "2") (pinfunction "2_2") (pintype "passive"))
    )
    (net (code "167") (name "Net-(J_CLKQUAD-Pad07)") (class "Default")
      (node (ref "J_CLKQUAD") (pin "07") (pinfunction "07_07") (pintype "passive"))
      (node (ref "R30") (pin "2") (pinfunction "2_2") (pintype "passive"))
    )
    (net (code "168") (name "Net-(J_CLKQUAD-Pad09)") (class "Default")
      (node (ref "J_CLKQUAD") (pin "09") (pinfunction "09_09") (pintype "passive"))
      (node (ref "R31") (pin "2") (pinfunction "2_2") (pintype "passive"))
    )
    (net (code "169") (name "Net-(P1-Pad1)") (class "Default")
      (node (ref "P1") (pin "1") (pinfunction "1_1") (pintype "passive"))
      (node (ref "R10") (pin "1") (pinfunction "1_1") (pintype "passive"))
    )
    (net (code "170") (name "Net-(P1V2_EN-Pad3)") (class "Default")
      (node (ref "P1V2_EN") (pin "3") (pinfunction "3_3") (pintype "passive"))
      (node (ref "R7") (pin "1") (pinfunction "1_1") (pintype "passive"))
      (node (ref "R9") (pin "1") (pinfunction "1_1") (pintype "passive"))
    )
    (net (code "171") (name "Net-(P1V2_POT-CCW)") (class "Default")
      (node (ref "P1") (pin "2") (pinfunction "2_2") (pintype "passive"))
      (node (ref "P1V2_POT") (pin "1") (pinfunction "CCW_1") (pintype "passive"))
      (node (ref "P1V2_POT") (pin "2") (pinfunction "WIPER_2") (pintype "passive"))
    )
    (net (code "172") (name "Net-(U5-EN)") (class "Default")
      (node (ref "P1V2_EN") (pin "2") (pinfunction "2_2") (pintype "passive"))
      (node (ref "U5") (pin "16") (pinfunction "EN_16") (pintype "input"))
    )
    (net (code "173") (name "Net-(U5-NR{slash}SS)") (class "Default")
      (node (ref "C13") (pin "1") (pinfunction "1_1") (pintype "passive"))
      (node (ref "U5") (pin "8") (pinfunction "NR/SS_8") (pintype "bidirectional"))
    )
    (net (code "174") (name "Net-(U5-REF)") (class "Default")
      (node (ref "P1") (pin "3") (pinfunction "3_3") (pintype "passive"))
      (node (ref "R10") (pin "2") (pinfunction "2_2") (pintype "passive"))
      (node (ref "U5") (pin "7") (pinfunction "REF_7") (pintype "bidirectional"))
    )
    (net (code "175") (name "Net-(U_LS1-A)") (class "Default")
      (node (ref "C3") (pin "2") (pinfunction "2_2") (pintype "passive"))
      (node (ref "R3") (pin "1") (pinfunction "1_1") (pintype "passive"))
      (node (ref "U_LS1") (pin "2") (pinfunction "A_2") (pintype "input"))
    )
    (net (code "176") (name "Net-(U_LS1-Y)") (class "Default")
      (node (ref "U_LS1") (pin "4") (pinfunction "Y_4") (pintype "output"))
      (node (ref "U_LS2") (pin "2") (pinfunction "A_2") (pintype "input"))
    )
    (net (code "177") (name "VCCO_MC1") (class "Default")
      (node (ref "J_VCCO_MC1") (pin "1") (pinfunction "1_1") (pintype "passive"))
      (node (ref "MC1") (pin "36") (pinfunction "36_36") (pintype "passive"))
      (node (ref "MC1") (pin "56") (pinfunction "56_56") (pintype "passive"))
      (node (ref "U2") (pin "13") (pinfunction "VCCB_13") (pintype "power_in"))
      (node (ref "U4") (pin "6") (pinfunction "VCCB_6") (pintype "power_in"))
    )
    (net (code "178") (name "unconnected-(J_ESHF-Pad43)") (class "Default")
      (node (ref "J_ESHF") (pin "43") (pinfunction "43_43") (pintype "passive+no_connect"))
    )
    (net (code "179") (name "unconnected-(J_JTAG-Pad12)") (class "Default")
      (node (ref "J_JTAG") (pin "12") (pinfunction "12_12") (pintype "passive+no_connect"))
    )
    (net (code "180") (name "unconnected-(J_JTAG-Pad14)") (class "Default")
      (node (ref "J_JTAG") (pin "14") (pinfunction "14_14") (pintype "passive+no_connect"))
    )
    (net (code "181") (name "unconnected-(J_USB-ID-Pad4)") (class "Default")
      (node (ref "J_USB") (pin "4") (pinfunction "ID_4") (pintype "passive+no_connect"))
    )
    (net (code "182") (name "unconnected-(MC1-Pad9)") (class "Default")
      (node (ref "MC1") (pin "9") (pinfunction "9_9") (pintype "passive+no_connect"))
    )
    (net (code "183") (name "unconnected-(MC1-Pad11)") (class "Default")
      (node (ref "MC1") (pin "11") (pinfunction "11_11") (pintype "passive+no_connect"))
    )
    (net (code "184") (name "unconnected-(MC1-Pad13)") (class "Default")
      (node (ref "MC1") (pin "13") (pinfunction "13_13") (pintype "passive+no_connect"))
    )
    (net (code "185") (name "unconnected-(MC1-Pad18)") (class "Default")
      (node (ref "MC1") (pin "18") (pinfunction "18_18") (pintype "passive+no_connect"))
    )
    (net (code "186") (name "unconnected-(MC1-Pad22)") (class "Default")
      (node (ref "MC1") (pin "22") (pinfunction "22_22") (pintype "passive+no_connect"))
    )
    (net (code "187") (name "unconnected-(MC1-Pad26)") (class "Default")
      (node (ref "MC1") (pin "26") (pinfunction "26_26") (pintype "passive+no_connect"))
    )
    (net (code "188") (name "unconnected-(MC1-Pad30)") (class "Default")
      (node (ref "MC1") (pin "30") (pinfunction "30_30") (pintype "passive+no_connect"))
    )
    (net (code "189") (name "unconnected-(MC1-Pad34)") (class "Default")
      (node (ref "MC1") (pin "34") (pinfunction "34_34") (pintype "passive+no_connect"))
    )
    (net (code "190") (name "unconnected-(MC1-Pad42)") (class "Default")
      (node (ref "MC1") (pin "42") (pinfunction "42_42") (pintype "passive+no_connect"))
    )
    (net (code "191") (name "unconnected-(MC2-Pad2)") (class "Default")
      (node (ref "MC2") (pin "2") (pinfunction "2_2") (pintype "passive+no_connect"))
    )
    (net (code "192") (name "unconnected-(MC2-Pad4)") (class "Default")
      (node (ref "MC2") (pin "4") (pinfunction "4_4") (pintype "passive+no_connect"))
    )
    (net (code "193") (name "unconnected-(MC2-Pad6)") (class "Default")
      (node (ref "MC2") (pin "6") (pinfunction "6_6") (pintype "passive+no_connect"))
    )
    (net (code "194") (name "unconnected-(MC2-Pad44)") (class "Default")
      (node (ref "MC2") (pin "44") (pinfunction "44_44") (pintype "passive+no_connect"))
    )
    (net (code "195") (name "unconnected-(MC2-Pad58)") (class "Default")
      (node (ref "MC2") (pin "58") (pinfunction "58_58") (pintype "passive+no_connect"))
    )
    (net (code "196") (name "unconnected-(MC2-Pad62)") (class "Default")
      (node (ref "MC2") (pin "62") (pinfunction "62_62") (pintype "passive+no_connect"))
    )
    (net (code "197") (name "unconnected-(MH1-Pad1)") (class "Default")
      (node (ref "MH1") (pin "1") (pinfunction "1_1") (pintype "passive+no_connect"))
    )
    (net (code "198") (name "unconnected-(MH2-Pad1)") (class "Default")
      (node (ref "MH2") (pin "1") (pinfunction "1_1") (pintype "passive+no_connect"))
    )
    (net (code "199") (name "unconnected-(MH3-Pad1)") (class "Default")
      (node (ref "MH3") (pin "1") (pinfunction "1_1") (pintype "passive+no_connect"))
    )
    (net (code "200") (name "unconnected-(MH4-Pad1)") (class "Default")
      (node (ref "MH4") (pin "1") (pinfunction "1_1") (pintype "passive+no_connect"))
    )
    (net (code "201") (name "unconnected-(MH5-Pad1)") (class "Default")
      (node (ref "MH5") (pin "1") (pinfunction "1_1") (pintype "passive+no_connect"))
    )
    (net (code "202") (name "unconnected-(MH6-Pad1)") (class "Default")
      (node (ref "MH6") (pin "1") (pinfunction "1_1") (pintype "passive+no_connect"))
    )
    (net (code "203") (name "unconnected-(MH7-Pad1)") (class "Default")
      (node (ref "MH7") (pin "1") (pinfunction "1_1") (pintype "passive+no_connect"))
    )
    (net (code "204") (name "unconnected-(MH8-Pad1)") (class "Default")
      (node (ref "MH8") (pin "1") (pinfunction "1_1") (pintype "passive+no_connect"))
    )
    (net (code "205") (name "unconnected-(U3-GP0-Pad2)") (class "Default")
      (node (ref "U3") (pin "2") (pinfunction "GP0_2") (pintype "bidirectional+no_connect"))
    )
    (net (code "206") (name "unconnected-(U3-GP1-Pad3)") (class "Default")
      (node (ref "U3") (pin "3") (pinfunction "GP1_3") (pintype "bidirectional+no_connect"))
    )
    (net (code "207") (name "unconnected-(U3-GP2-Pad7)") (class "Default")
      (node (ref "U3") (pin "7") (pinfunction "GP2_7") (pintype "bidirectional+no_connect"))
    )
    (net (code "208") (name "unconnected-(U3-GP3-Pad8)") (class "Default")
      (node (ref "U3") (pin "8") (pinfunction "GP3_8") (pintype "bidirectional+no_connect"))
    )
    (net (code "209") (name "unconnected-(U3-URX-Pad5)") (class "Default")
      (node (ref "U3") (pin "5") (pinfunction "URX_5") (pintype "input+no_connect"))
    )
    (net (code "210") (name "unconnected-(U3-UTX-Pad6)") (class "Default")
      (node (ref "U3") (pin "6") (pinfunction "UTX_6") (pintype "output+no_connect"))
    )
    (net (code "211") (name "unconnected-(U3-~{RST}-Pad4)") (class "Default")
      (node (ref "U3") (pin "4") (pinfunction "~{RST}_4") (pintype "output"))
    )
    (net (code "212") (name "unconnected-(U5-BIAS-Pad5)") (class "Default")
      (node (ref "U5") (pin "5") (pinfunction "BIAS_5") (pintype "input+no_connect"))
    )
    (net (code "213") (name "unconnected-(U_LS1-NC-Pad1)") (class "Default")
      (node (ref "U_LS1") (pin "1") (pinfunction "NC_1") (pintype "passive+no_connect"))
    )
    (net (code "214") (name "unconnected-(U_LS2-NC-Pad1)") (class "Default")
      (node (ref "U_LS2") (pin "1") (pinfunction "NC_1") (pintype "passive+no_connect"))
    )
  )
)
